# Flyback_circuit_2024-07-31.net
KiCad netlist of a schematic drawn in EasyEDA Pro
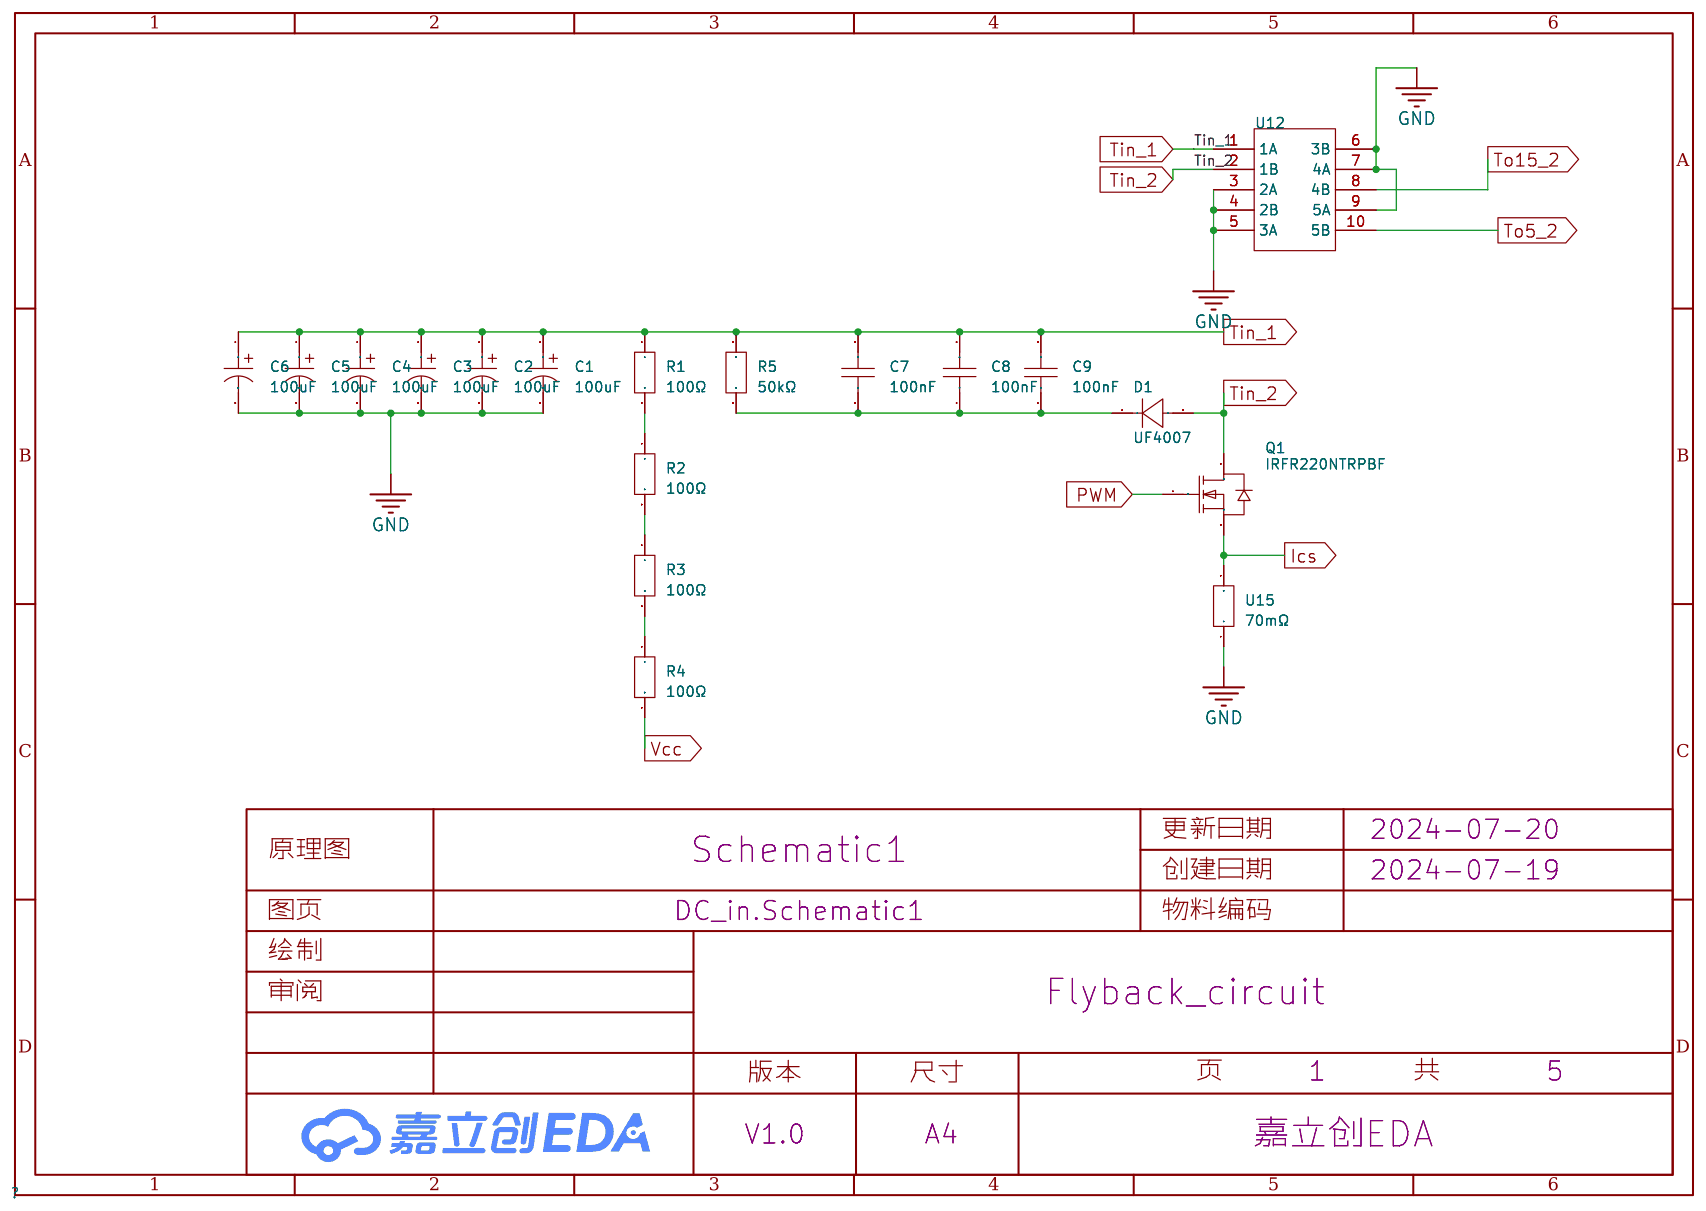
[diagram p0: DC_in]
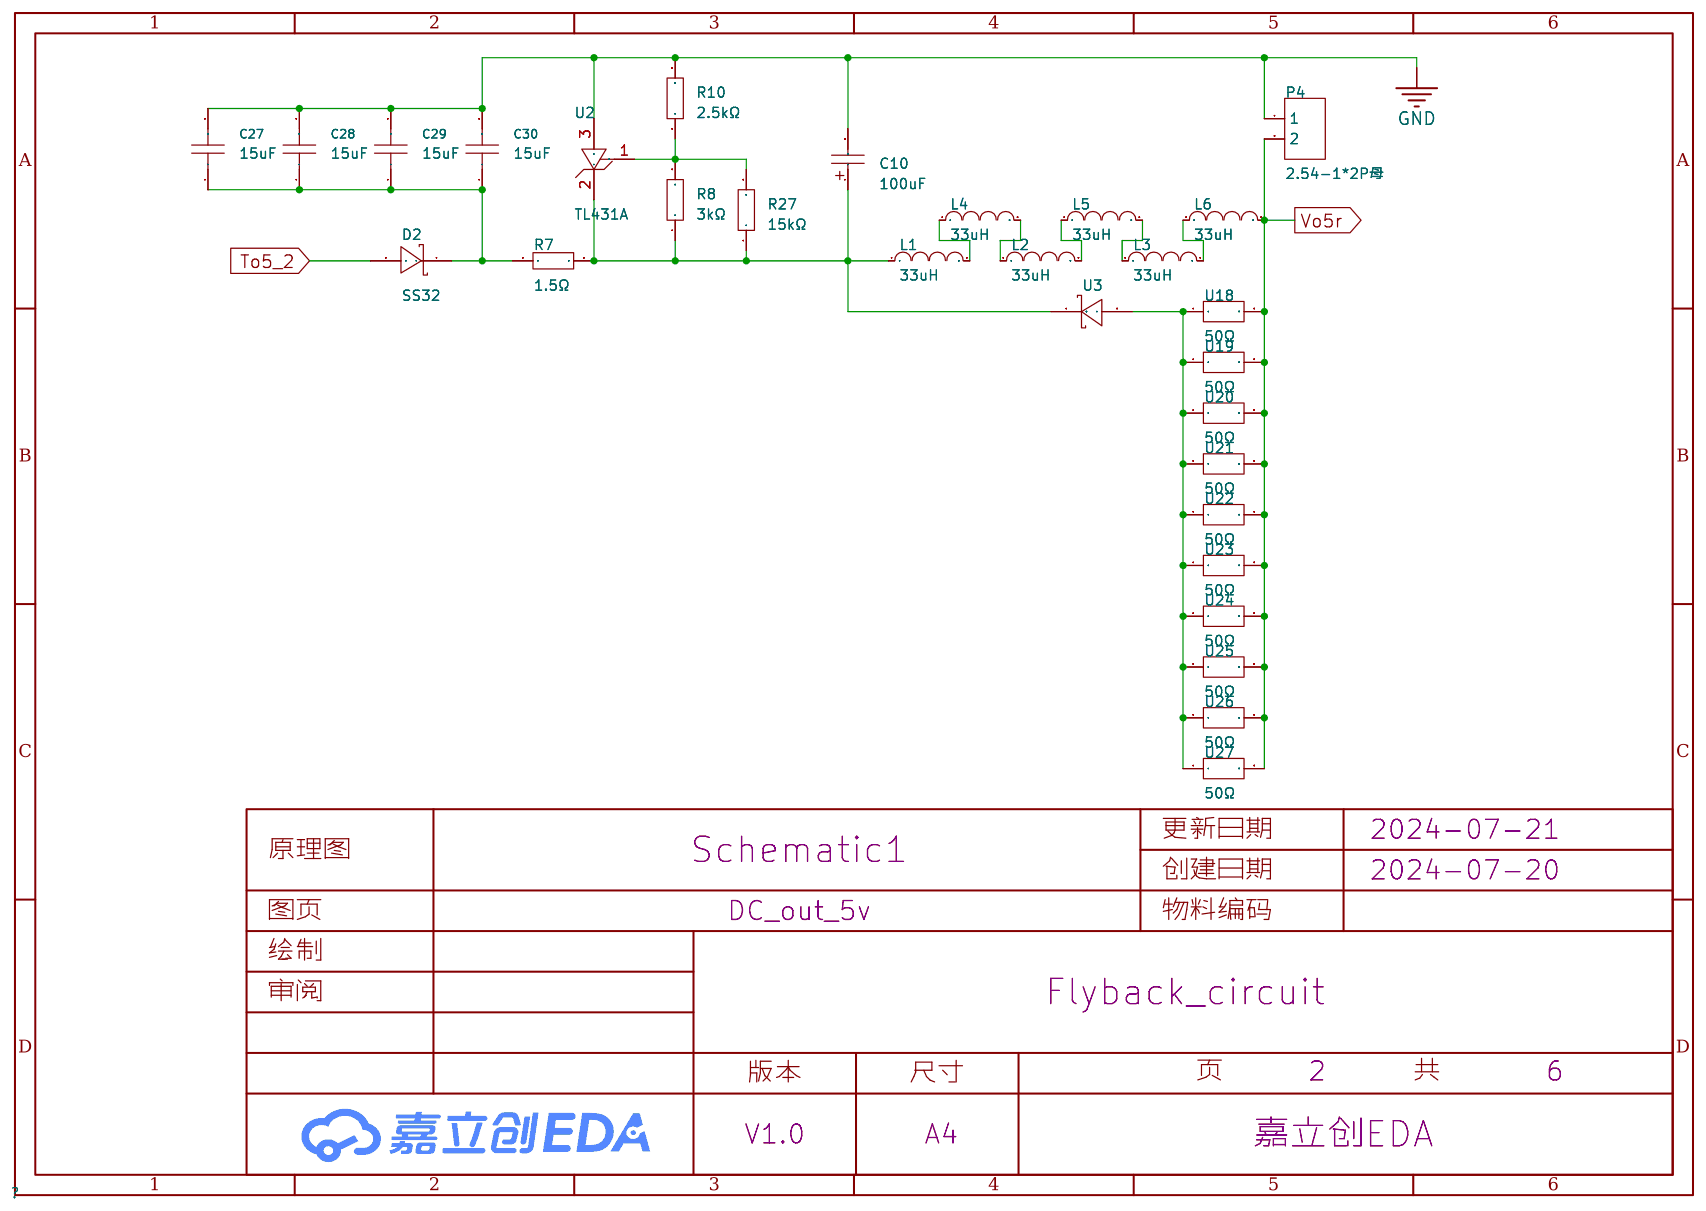
[diagram p1: DC_out_5v]
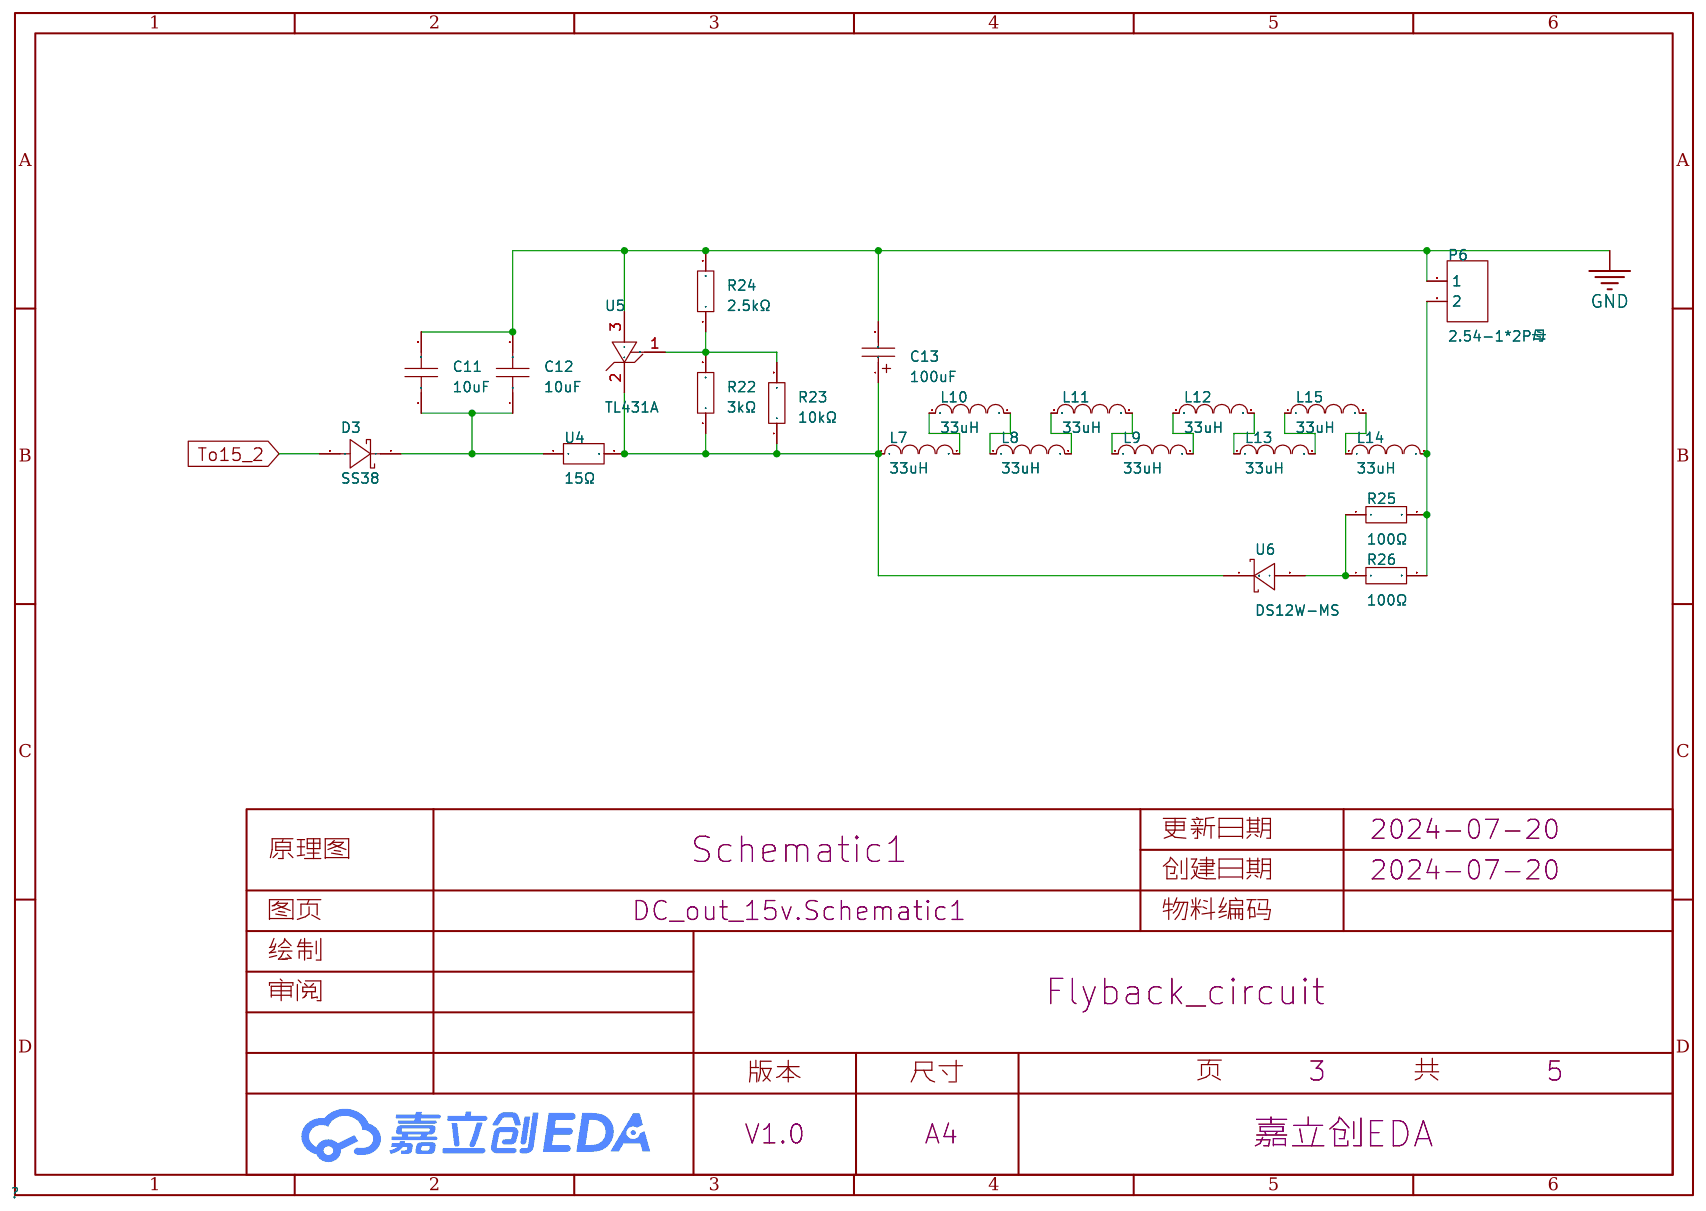
[diagram p2: DC_out_15v]
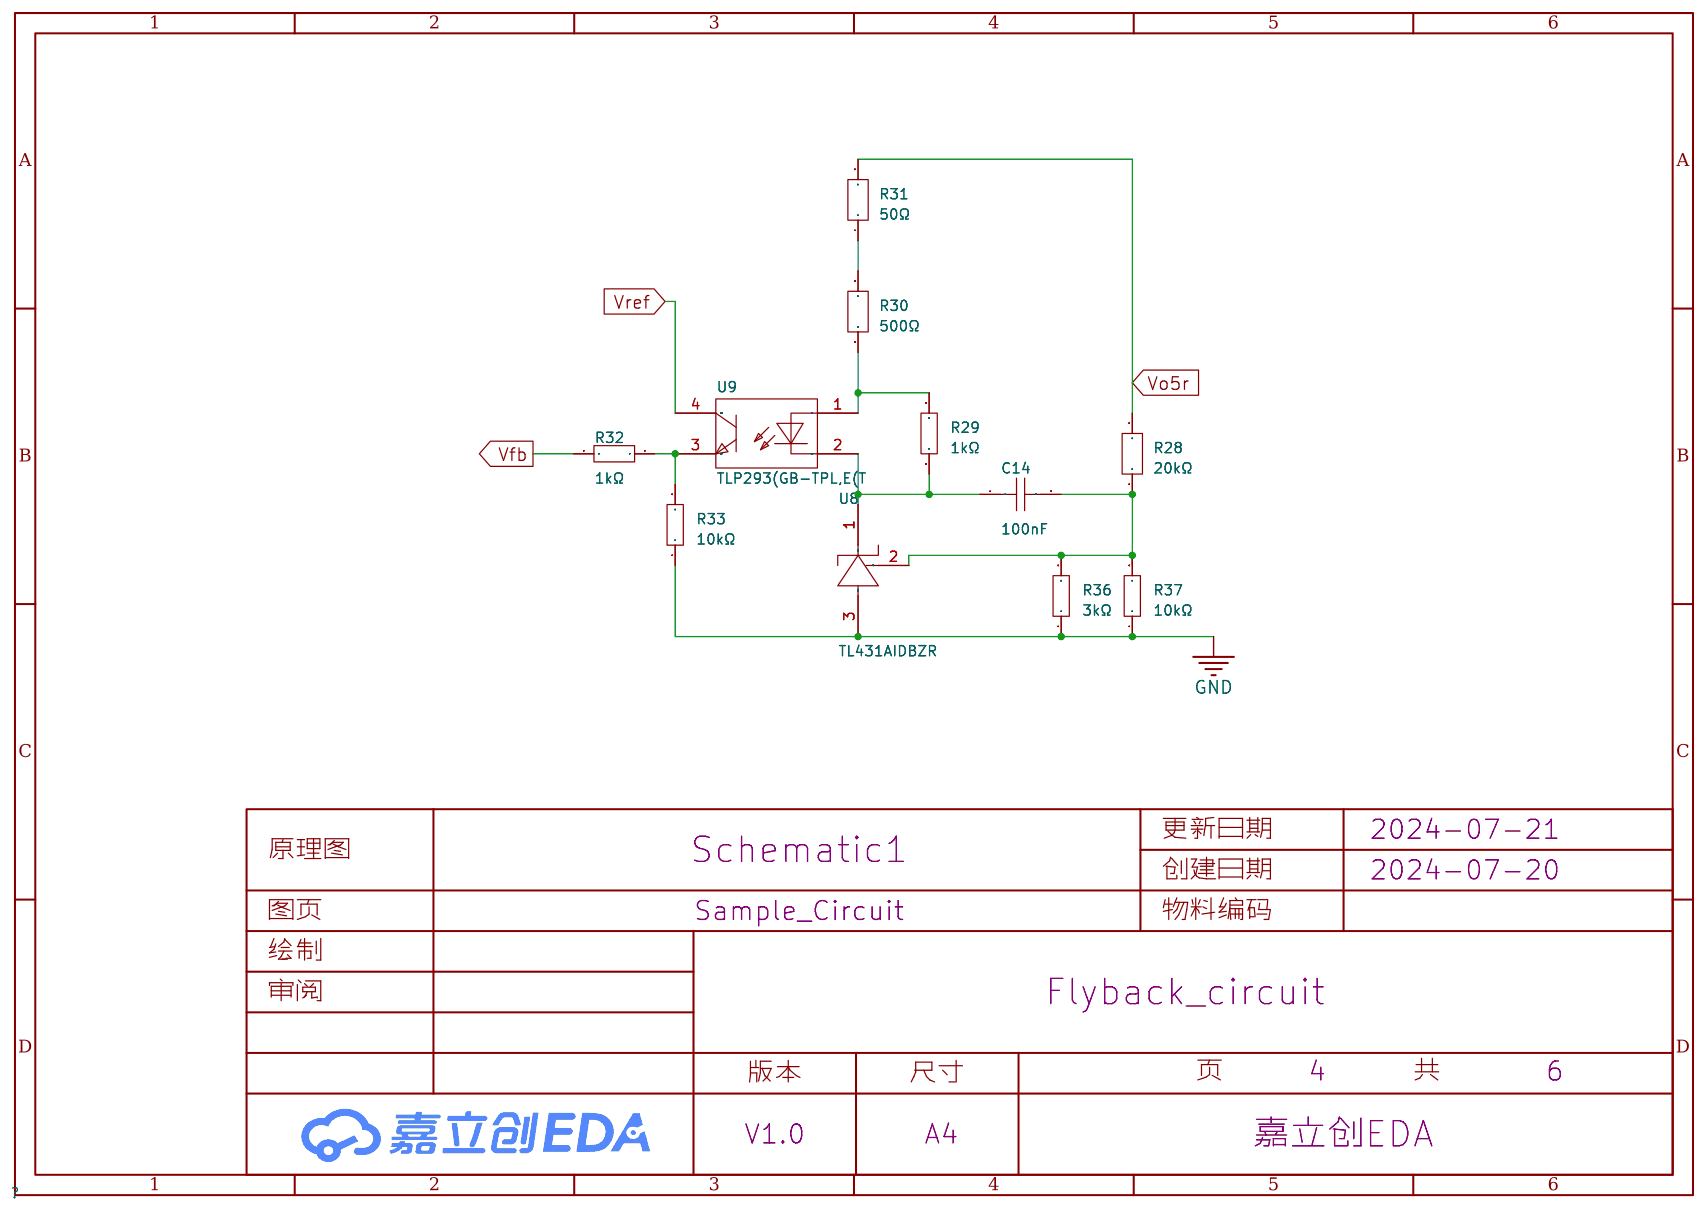
[diagram p3: Sample_Circuit]
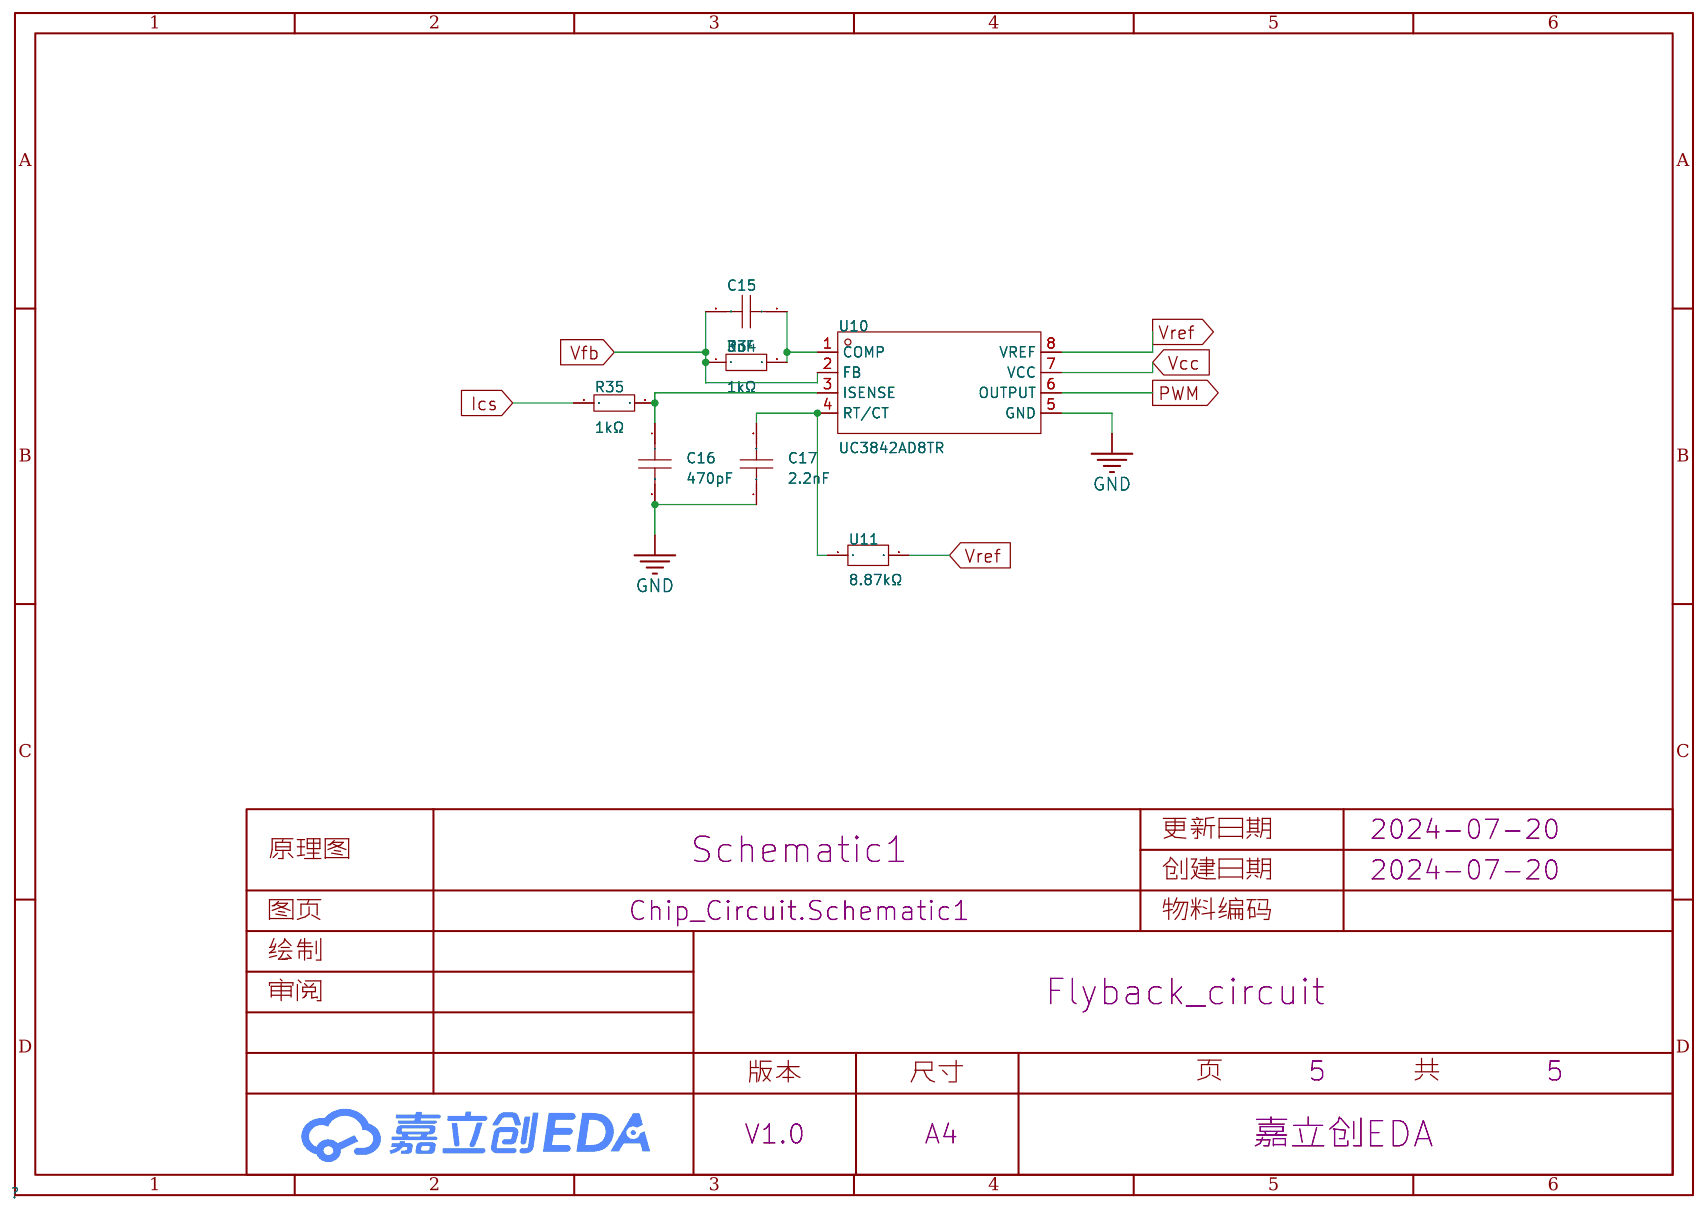
[diagram p4: Chip_Circuit]
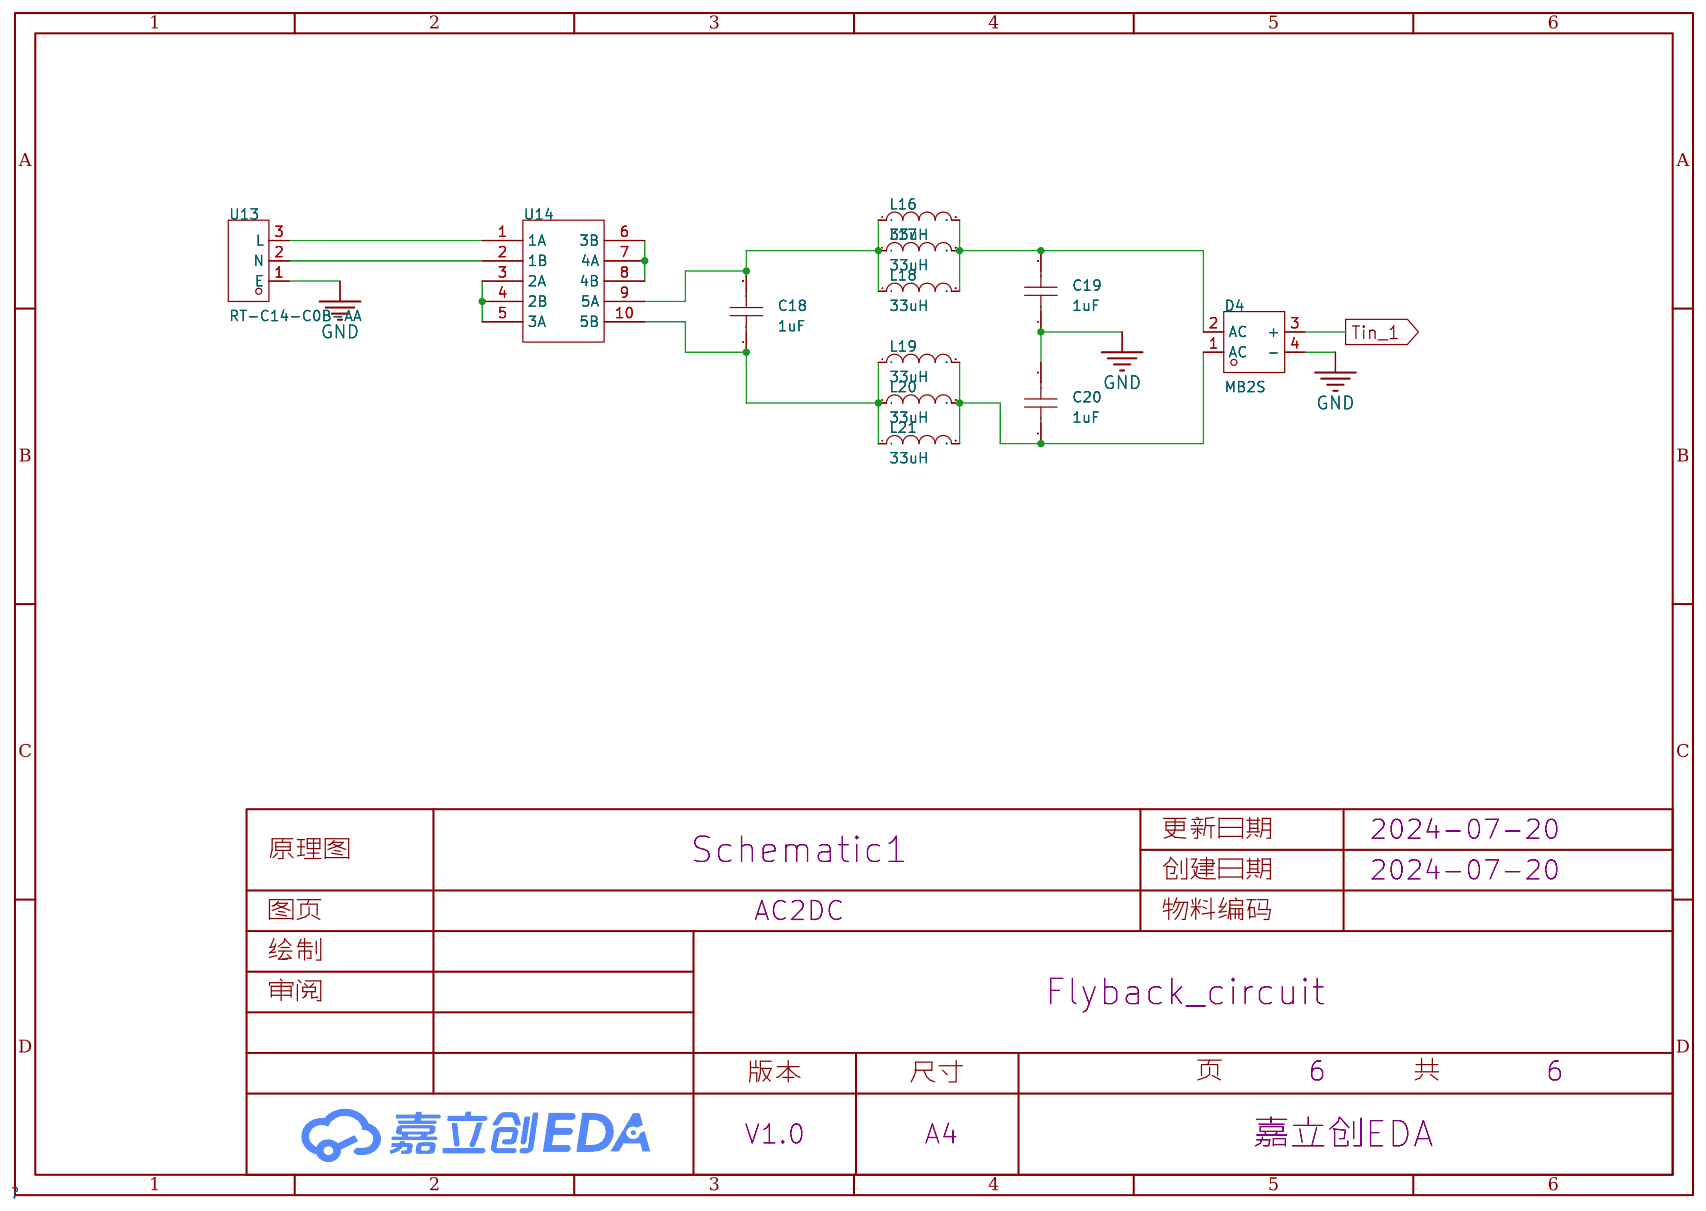
[diagram p5: AC2DC]

(export (version "E")
  (design (tool "Eeschema 10.0.6"))
  (components
    (comp (ref "C1")
      (value "100uF")
      (footprint "easyedapro:CAP-SMD_BD6.3-L6.6-W6.6-LS7.4-FD")
      (description "容值:100uF;精度:±20%;额定电压:35V;纹波电流:87mA@120kHz;等效串联电阻:-;")
      (fields
        (field (name "Manufacturer Part") "RVT100UF35V67RV0034")
        (field (name "Manufacturer") "KNSCHA(科尼盛)")
      )
      (libsource (lib "easyedapro") (part "RVT100UF35V67RV0034"))
    )
    (comp (ref "C2")
      (value "100uF")
      (footprint "easyedapro:CAP-SMD_BD6.3-L6.6-W6.6-LS7.4-FD")
      (description "容值:100uF;精度:±20%;额定电压:35V;纹波电流:87mA@120kHz;等效串联电阻:-;")
      (fields
        (field (name "Manufacturer Part") "RVT100UF35V67RV0034")
        (field (name "Manufacturer") "KNSCHA(科尼盛)")
      )
      (libsource (lib "easyedapro") (part "RVT100UF35V67RV0034"))
    )
    (comp (ref "C3")
      (value "100uF")
      (footprint "easyedapro:CAP-SMD_BD6.3-L6.6-W6.6-LS7.4-FD")
      (description "容值:100uF;精度:±20%;额定电压:35V;纹波电流:87mA@120kHz;等效串联电阻:-;")
      (fields
        (field (name "Manufacturer Part") "RVT100UF35V67RV0034")
        (field (name "Manufacturer") "KNSCHA(科尼盛)")
      )
      (libsource (lib "easyedapro") (part "RVT100UF35V67RV0034"))
    )
    (comp (ref "C4")
      (value "100uF")
      (footprint "easyedapro:CAP-SMD_BD6.3-L6.6-W6.6-LS7.4-FD")
      (description "容值:100uF;精度:±20%;额定电压:35V;纹波电流:87mA@120kHz;等效串联电阻:-;")
      (fields
        (field (name "Manufacturer Part") "RVT100UF35V67RV0034")
        (field (name "Manufacturer") "KNSCHA(科尼盛)")
      )
      (libsource (lib "easyedapro") (part "RVT100UF35V67RV0034"))
    )
    (comp (ref "C5")
      (value "100uF")
      (footprint "easyedapro:CAP-SMD_BD6.3-L6.6-W6.6-LS7.4-FD")
      (description "容值:100uF;精度:±20%;额定电压:35V;纹波电流:87mA@120kHz;等效串联电阻:-;")
      (fields
        (field (name "Manufacturer Part") "RVT100UF35V67RV0034")
        (field (name "Manufacturer") "KNSCHA(科尼盛)")
      )
      (libsource (lib "easyedapro") (part "RVT100UF35V67RV0034"))
    )
    (comp (ref "C6")
      (value "100uF")
      (footprint "easyedapro:CAP-SMD_BD6.3-L6.6-W6.6-LS7.4-FD")
      (description "容值:100uF;精度:±20%;额定电压:35V;纹波电流:87mA@120kHz;等效串联电阻:-;")
      (fields
        (field (name "Manufacturer Part") "RVT100UF35V67RV0034")
        (field (name "Manufacturer") "KNSCHA(科尼盛)")
      )
      (libsource (lib "easyedapro") (part "RVT100UF35V67RV0034"))
    )
    (comp (ref "C7")
      (value "100nF")
      (footprint "easyedapro:C0603")
      (description "容值:100nF;精度:±10%;额定电压:50V;材质(温度系数):X7R;")
      (fields
        (field (name "Manufacturer Part") "CC0603KRX7R9BB104")
        (field (name "Manufacturer") "YAGEO(国巨)")
      )
      (libsource (lib "easyedapro") (part "CC0603KRX7R9BB104"))
    )
    (comp (ref "C8")
      (value "100nF")
      (footprint "easyedapro:C0603")
      (description "容值:100nF;精度:±10%;额定电压:50V;材质(温度系数):X7R;")
      (fields
        (field (name "Manufacturer Part") "CC0603KRX7R9BB104")
        (field (name "Manufacturer") "YAGEO(国巨)")
      )
      (libsource (lib "easyedapro") (part "CC0603KRX7R9BB104"))
    )
    (comp (ref "C9")
      (value "100nF")
      (footprint "easyedapro:C0603")
      (description "容值:100nF;精度:±10%;额定电压:50V;材质(温度系数):X7R;")
      (fields
        (field (name "Manufacturer Part") "CC0603KRX7R9BB104")
        (field (name "Manufacturer") "YAGEO(国巨)")
      )
      (libsource (lib "easyedapro") (part "CC0603KRX7R9BB104"))
    )
    (comp (ref "D1")
      (value "UF4007")
      (footprint "easyedapro:DO-41_BD2.4-L4.7-P8.70-D0.9-RD")
      (description "二极管配置:-;正向压降(Vf):1.7V@1A;直流反向耐压(Vr):1kV;整流电流:1A;反向恢复时间(trr):75ns;")
      (fields (field (name "Manufacturer") "MDD(辰达半导体)"))
      (libsource (lib "easyedapro") (part "UF4007_C960666"))
    )
    (comp (ref "Q1")
      (value "IRFR220NTRPBF")
      (footprint "easyedapro:TO-252-2_L6.6-W6.1-P4.57-LS9.9-TR-CW")
      (fields (field (name "Manufacturer") "Infineon(英飞凌)"))
      (libsource (lib "easyedapro") (part "IRFR220N"))
    )
    (comp (ref "R1")
      (value "100Ω")
      (footprint "easyedapro:R2010")
      (description "电阻类型:厚膜电阻;阻值:100Ω;精度:±5%;功率:1.5W;最大工作电压:400V;温度系数:±100ppm/°C;")
      (fields
        (field (name "Manufacturer Part") "AS101AJ0101T4E")
        (field (name "Manufacturer") "UNI-ROYAL(厚声)")
      )
      (libsource (lib "easyedapro") (part "AS101AJ0101T4E"))
    )
    (comp (ref "R2")
      (value "100Ω")
      (footprint "easyedapro:R2010")
      (description "电阻类型:厚膜电阻;阻值:100Ω;精度:±5%;功率:1.5W;最大工作电压:400V;温度系数:±100ppm/°C;")
      (fields
        (field (name "Manufacturer Part") "AS101AJ0101T4E")
        (field (name "Manufacturer") "UNI-ROYAL(厚声)")
      )
      (libsource (lib "easyedapro") (part "AS101AJ0101T4E"))
    )
    (comp (ref "R3")
      (value "100Ω")
      (footprint "easyedapro:R2010")
      (description "电阻类型:厚膜电阻;阻值:100Ω;精度:±5%;功率:1.5W;最大工作电压:400V;温度系数:±100ppm/°C;")
      (fields
        (field (name "Manufacturer Part") "AS101AJ0101T4E")
        (field (name "Manufacturer") "UNI-ROYAL(厚声)")
      )
      (libsource (lib "easyedapro") (part "AS101AJ0101T4E"))
    )
    (comp (ref "R4")
      (value "100Ω")
      (footprint "easyedapro:R2010")
      (description "电阻类型:厚膜电阻;阻值:100Ω;精度:±5%;功率:1.5W;最大工作电压:400V;温度系数:±100ppm/°C;")
      (fields
        (field (name "Manufacturer Part") "AS101AJ0101T4E")
        (field (name "Manufacturer") "UNI-ROYAL(厚声)")
      )
      (libsource (lib "easyedapro") (part "AS101AJ0101T4E"))
    )
    (comp (ref "R5")
      (value "50kΩ")
      (footprint "easyedapro:R0805")
      (description "电阻类型:薄膜电阻;阻值:50kΩ;精度:±0.5%;功率:125mW;最大工作电压:150V;温度系数:±25ppm/°C;")
      (fields (field (name "Manufacturer Part") "ARG05DTC5002") (field (name "Manufacturer") "Viking(光颉)"))
      (libsource (lib "easyedapro") (part "ARG05DTC5002"))
    )
    (comp (ref "U12")
      (value "~")
      (footprint "easyedapro:反激变压器_封装")
      (libsource (lib "easyedapro") (part "反激变压器_自定义"))
    )
    (comp (ref "U15")
      (value "70mΩ")
      (footprint "easyedapro:R1206")
      (description "电阻类型:薄膜电阻;阻值:70mΩ;精度:±1%;功率:500mW;最大工作电压:-;温度系数:±75ppm/°C;")
      (fields (field (name "Manufacturer Part") "PE1206FRM7W0R07L") (field (name "Manufacturer") "YAGEO(国巨)"))
      (libsource (lib "easyedapro") (part "PE1206FRM7W0R07L"))
    )
    (comp (ref "C10")
      (value "100uF")
      (footprint "easyedapro:CAP-SMD_L3.5-W2.8-R-RD")
      (description "容值:100uF;精度:±10%;额定电压:10V;等效串联电阻:1.4Ω@100kHz;")
      (fields (field (name "Manufacturer Part") "CA45-B010K107T") (field (name "Manufacturer") "湘怡中元/湘江"))
      (libsource (lib "easyedapro") (part "CA45-B010K107T"))
    )
    (comp (ref "C27")
      (value "15uF")
      (footprint "easyedapro:CAP-TH_L5.5-W4.0-P2.50-D1.0")
      (description "容值:15uF;精度:±20%;额定电压:16V;温度系数:X7R;")
      (fields (field (name "Manufacturer Part") "FG11X7R1C156MRT06") (field (name "Manufacturer") "TDK"))
      (libsource (lib "easyedapro") (part "FG11X7R1C156MRT06"))
    )
    (comp (ref "C28")
      (value "15uF")
      (footprint "easyedapro:CAP-TH_L5.5-W4.0-P2.50-D1.0")
      (description "容值:15uF;精度:±20%;额定电压:16V;温度系数:X7R;")
      (fields (field (name "Manufacturer Part") "FG11X7R1C156MRT06") (field (name "Manufacturer") "TDK"))
      (libsource (lib "easyedapro") (part "FG11X7R1C156MRT06"))
    )
    (comp (ref "C29")
      (value "15uF")
      (footprint "easyedapro:CAP-TH_L5.5-W4.0-P2.50-D1.0")
      (description "容值:15uF;精度:±20%;额定电压:16V;温度系数:X7R;")
      (fields (field (name "Manufacturer Part") "FG11X7R1C156MRT06") (field (name "Manufacturer") "TDK"))
      (libsource (lib "easyedapro") (part "FG11X7R1C156MRT06"))
    )
    (comp (ref "C30")
      (value "15uF")
      (footprint "easyedapro:CAP-TH_L5.5-W4.0-P2.50-D1.0")
      (description "容值:15uF;精度:±20%;额定电压:16V;温度系数:X7R;")
      (fields (field (name "Manufacturer Part") "FG11X7R1C156MRT06") (field (name "Manufacturer") "TDK"))
      (libsource (lib "easyedapro") (part "FG11X7R1C156MRT06"))
    )
    (comp (ref "D2")
      (value "SS32")
      (footprint "easyedapro:SMA_L4.3-W2.6-LS5.2-RD")
      (description "二极管配置:独立式;正向压降(Vf):550mV@3A;直流反向耐压(Vr):20V;整流电流:3A;")
      (fields (field (name "Manufacturer") "MDD(辰达半导体)"))
      (libsource (lib "easyedapro") (part "SS32_C34897"))
    )
    (comp (ref "L1")
      (value "33uH")
      (footprint "easyedapro:IND-SMD_L7.0-W6.6_FXL0630")
      (description "电感值:33uH;精度:±20%;额定电流:2A;饱和电流(Isat):2.5A;类型:一体成型电感;")
      (fields (field (name "Manufacturer Part") "FXL0630-330-M") (field (name "Manufacturer") "cjiang(长江微电)"))
      (libsource (lib "easyedapro") (part "FXL0630-330-M"))
    )
    (comp (ref "L2")
      (value "33uH")
      (footprint "easyedapro:IND-SMD_L7.0-W6.6_FXL0630")
      (description "电感值:33uH;精度:±20%;额定电流:2A;饱和电流(Isat):2.5A;类型:一体成型电感;")
      (fields (field (name "Manufacturer Part") "FXL0630-330-M") (field (name "Manufacturer") "cjiang(长江微电)"))
      (libsource (lib "easyedapro") (part "FXL0630-330-M"))
    )
    (comp (ref "L3")
      (value "33uH")
      (footprint "easyedapro:IND-SMD_L7.0-W6.6_FXL0630")
      (description "电感值:33uH;精度:±20%;额定电流:2A;饱和电流(Isat):2.5A;类型:一体成型电感;")
      (fields (field (name "Manufacturer Part") "FXL0630-330-M") (field (name "Manufacturer") "cjiang(长江微电)"))
      (libsource (lib "easyedapro") (part "FXL0630-330-M"))
    )
    (comp (ref "L4")
      (value "33uH")
      (footprint "easyedapro:IND-SMD_L7.0-W6.6_FXL0630")
      (description "电感值:33uH;精度:±20%;额定电流:2A;饱和电流(Isat):2.5A;类型:一体成型电感;")
      (fields (field (name "Manufacturer Part") "FXL0630-330-M") (field (name "Manufacturer") "cjiang(长江微电)"))
      (libsource (lib "easyedapro") (part "FXL0630-330-M"))
    )
    (comp (ref "L5")
      (value "33uH")
      (footprint "easyedapro:IND-SMD_L7.0-W6.6_FXL0630")
      (description "电感值:33uH;精度:±20%;额定电流:2A;饱和电流(Isat):2.5A;类型:一体成型电感;")
      (fields (field (name "Manufacturer Part") "FXL0630-330-M") (field (name "Manufacturer") "cjiang(长江微电)"))
      (libsource (lib "easyedapro") (part "FXL0630-330-M"))
    )
    (comp (ref "L6")
      (value "33uH")
      (footprint "easyedapro:IND-SMD_L7.0-W6.6_FXL0630")
      (description "电感值:33uH;精度:±20%;额定电流:2A;饱和电流(Isat):2.5A;类型:一体成型电感;")
      (fields (field (name "Manufacturer Part") "FXL0630-330-M") (field (name "Manufacturer") "cjiang(长江微电)"))
      (libsource (lib "easyedapro") (part "FXL0630-330-M"))
    )
    (comp (ref "P4")
      (value "2.54-1*2P母")
      (footprint "easyedapro:HDR-TH_2P-P2.54-V-F")
      (description "插孔结构:1x2P;间距:2.54mm;行距:-;安装类型:直插;排数:单排;总孔位数:2P;塑高:-;触头材质:-;触头镀层:-;")
      (fields (field (name "Manufacturer") "BOOMELE(博穆精密)"))
      (libsource (lib "easyedapro") (part "Header-Female-2.54_1x2"))
    )
    (comp (ref "R7")
      (value "1.5Ω")
      (footprint "easyedapro:RES-TH_BD1.9-L3.3-P7.30-D0.5")
      (description "电阻类型:金属膜电阻;阻值:1.5Ω;精度:±1%;功率:166.667mW;温度系数:±100ppm/°C;")
      (fields (field (name "Manufacturer Part") "RN16T51R50F") (field (name "Manufacturer") "大毅科技"))
      (libsource (lib "easyedapro") (part "RN16T51R50F"))
    )
    (comp (ref "R8")
      (value "3kΩ")
      (footprint "easyedapro:R0402")
      (description "电阻类型:薄膜电阻;阻值:3kΩ;精度:±0.1%;功率:62.5mW;最大工作电压:50V;温度系数:±25ppm/°C;")
      (fields (field (name "Manufacturer Part") "RT0402BRD073KL") (field (name "Manufacturer") "YAGEO(国巨)"))
      (libsource (lib "easyedapro") (part "RT0402BRD073KL"))
    )
    (comp (ref "R10")
      (value "2.5kΩ")
      (footprint "easyedapro:R0603")
      (description "阻值:2.5kΩ;精度:±0.1%;功率:62.5mW;温度系数:±25ppm/°C;")
      (fields (field (name "Manufacturer Part") "AR03BTC2501") (field (name "Manufacturer") "Viking(光颉)"))
      (libsource (lib "easyedapro") (part "AR03BTC2501"))
    )
    (comp (ref "R27")
      (value "15kΩ")
      (footprint "easyedapro:R0603")
      (description "电阻类型:厚膜电阻;阻值:15kΩ;精度:±1%;功率:100mW;最大工作电压:75V;温度系数:±100ppm/°C;")
      (fields
        (field (name "Manufacturer Part") "0603WAF1502T5E")
        (field (name "Manufacturer") "UNI-ROYAL(厚声)")
      )
      (libsource (lib "easyedapro") (part "0603WAF1502T5E"))
    )
    (comp (ref "U2")
      (value "TL431A")
      (footprint "easyedapro:SOT-23-3_L2.9-W1.3-P1.90-LS2.4-BR")
      (description "输出类型:可调;输入电压:37V;输出电压:2.495V~36V;输出电流:100mA;精度:±0.5%;")
      (fields (field (name "Manufacturer") "PJSEMI(平晶微)"))
      (libsource (lib "easyedapro") (part "TL431A_C411753"))
    )
    (comp (ref "U3")
      (value "DS12W-MS")
      (footprint "easyedapro:SOD-123FL_L2.7-W1.8-LS3.8-RD")
      (description "二极管配置:独立式;正向压降(Vf):550mV@1A;直流反向耐压(Vr):20V;平均整流电流(Io):1A;")
      (fields (field (name "Manufacturer") "MSKSEMI(美森科)"))
      (libsource (lib "easyedapro") (part "DS12W-MS"))
    )
    (comp (ref "U18")
      (value "50Ω")
      (footprint "easyedapro:R0603")
      (description "电阻类型:薄膜电阻;阻值:50Ω;精度:±0.1%;功率:100mW;温度系数:±50ppm/°C;")
      (fields (field (name "Manufacturer Part") "RT0603BRE0750RL") (field (name "Manufacturer") "YAGEO(国巨)"))
      (libsource (lib "easyedapro") (part "RT0603BRE0750RL"))
    )
    (comp (ref "U19")
      (value "50Ω")
      (footprint "easyedapro:R0603")
      (description "电阻类型:薄膜电阻;阻值:50Ω;精度:±0.1%;功率:100mW;温度系数:±50ppm/°C;")
      (fields (field (name "Manufacturer Part") "RT0603BRE0750RL") (field (name "Manufacturer") "YAGEO(国巨)"))
      (libsource (lib "easyedapro") (part "RT0603BRE0750RL"))
    )
    (comp (ref "U20")
      (value "50Ω")
      (footprint "easyedapro:R0603")
      (description "电阻类型:薄膜电阻;阻值:50Ω;精度:±0.1%;功率:100mW;温度系数:±50ppm/°C;")
      (fields (field (name "Manufacturer Part") "RT0603BRE0750RL") (field (name "Manufacturer") "YAGEO(国巨)"))
      (libsource (lib "easyedapro") (part "RT0603BRE0750RL"))
    )
    (comp (ref "U21")
      (value "50Ω")
      (footprint "easyedapro:R0603")
      (description "电阻类型:薄膜电阻;阻值:50Ω;精度:±0.1%;功率:100mW;温度系数:±50ppm/°C;")
      (fields (field (name "Manufacturer Part") "RT0603BRE0750RL") (field (name "Manufacturer") "YAGEO(国巨)"))
      (libsource (lib "easyedapro") (part "RT0603BRE0750RL"))
    )
    (comp (ref "U22")
      (value "50Ω")
      (footprint "easyedapro:R0603")
      (description "电阻类型:薄膜电阻;阻值:50Ω;精度:±0.1%;功率:100mW;温度系数:±50ppm/°C;")
      (fields (field (name "Manufacturer Part") "RT0603BRE0750RL") (field (name "Manufacturer") "YAGEO(国巨)"))
      (libsource (lib "easyedapro") (part "RT0603BRE0750RL"))
    )
    (comp (ref "U23")
      (value "50Ω")
      (footprint "easyedapro:R0603")
      (description "电阻类型:薄膜电阻;阻值:50Ω;精度:±0.1%;功率:100mW;温度系数:±50ppm/°C;")
      (fields (field (name "Manufacturer Part") "RT0603BRE0750RL") (field (name "Manufacturer") "YAGEO(国巨)"))
      (libsource (lib "easyedapro") (part "RT0603BRE0750RL"))
    )
    (comp (ref "U24")
      (value "50Ω")
      (footprint "easyedapro:R0603")
      (description "电阻类型:薄膜电阻;阻值:50Ω;精度:±0.1%;功率:100mW;温度系数:±50ppm/°C;")
      (fields (field (name "Manufacturer Part") "RT0603BRE0750RL") (field (name "Manufacturer") "YAGEO(国巨)"))
      (libsource (lib "easyedapro") (part "RT0603BRE0750RL"))
    )
    (comp (ref "U25")
      (value "50Ω")
      (footprint "easyedapro:R0603")
      (description "电阻类型:薄膜电阻;阻值:50Ω;精度:±0.1%;功率:100mW;温度系数:±50ppm/°C;")
      (fields (field (name "Manufacturer Part") "RT0603BRE0750RL") (field (name "Manufacturer") "YAGEO(国巨)"))
      (libsource (lib "easyedapro") (part "RT0603BRE0750RL"))
    )
    (comp (ref "U26")
      (value "50Ω")
      (footprint "easyedapro:R0603")
      (description "电阻类型:薄膜电阻;阻值:50Ω;精度:±0.1%;功率:100mW;温度系数:±50ppm/°C;")
      (fields (field (name "Manufacturer Part") "RT0603BRE0750RL") (field (name "Manufacturer") "YAGEO(国巨)"))
      (libsource (lib "easyedapro") (part "RT0603BRE0750RL"))
    )
    (comp (ref "U27")
      (value "50Ω")
      (footprint "easyedapro:R0603")
      (description "电阻类型:薄膜电阻;阻值:50Ω;精度:±0.1%;功率:100mW;温度系数:±50ppm/°C;")
      (fields (field (name "Manufacturer Part") "RT0603BRE0750RL") (field (name "Manufacturer") "YAGEO(国巨)"))
      (libsource (lib "easyedapro") (part "RT0603BRE0750RL"))
    )
    (comp (ref "C11")
      (value "10uF")
      (footprint "easyedapro:C1210")
      (description "容值:10uF;精度:±10%;额定电压:100V;材质(温度系数):X7R;")
      (fields (field (name "Manufacturer Part") "FS32X106K101EGG") (field (name "Manufacturer") "PSA(信昌电陶)"))
      (libsource (lib "easyedapro") (part "FS32X106K101EGG"))
    )
    (comp (ref "C12")
      (value "10uF")
      (footprint "easyedapro:C1210")
      (description "容值:10uF;精度:±10%;额定电压:100V;材质(温度系数):X7R;")
      (fields (field (name "Manufacturer Part") "FS32X106K101EGG") (field (name "Manufacturer") "PSA(信昌电陶)"))
      (libsource (lib "easyedapro") (part "FS32X106K101EGG"))
    )
    (comp (ref "C13")
      (value "100uF")
      (footprint "easyedapro:CASE-D_7343")
      (description "容值:100uF;精度:±10%;额定电压:20V;等效串联电阻:500mΩ@100kHz;")
      (fields (field (name "Manufacturer Part") "TAJD107K020RNJ") (field (name "Manufacturer") "Kyocera AVX"))
      (libsource (lib "easyedapro") (part "TAJD107K020RNJ"))
    )
    (comp (ref "D3")
      (value "SS38")
      (footprint "easyedapro:SMA_L4.3-W2.6-LS5.0-RD")
      (description "二极管配置:独立式;正向压降(Vf):850mV@3A;直流反向耐压(Vr):80V;平均整流电流(Io):3A;")
      (fields (field (name "Manufacturer") "宏迦橙"))
      (libsource (lib "easyedapro") (part "SS38_C18199196"))
    )
    (comp (ref "L7")
      (value "33uH")
      (footprint "easyedapro:IND-SMD_L7.0-W6.6_FXL0630")
      (description "电感值:33uH;精度:±20%;额定电流:2A;饱和电流(Isat):2.5A;类型:一体成型电感;")
      (fields (field (name "Manufacturer Part") "FXL0630-330-M") (field (name "Manufacturer") "cjiang(长江微电)"))
      (libsource (lib "easyedapro") (part "FXL0630-330-M"))
    )
    (comp (ref "L8")
      (value "33uH")
      (footprint "easyedapro:IND-SMD_L7.0-W6.6_FXL0630")
      (description "电感值:33uH;精度:±20%;额定电流:2A;饱和电流(Isat):2.5A;类型:一体成型电感;")
      (fields (field (name "Manufacturer Part") "FXL0630-330-M") (field (name "Manufacturer") "cjiang(长江微电)"))
      (libsource (lib "easyedapro") (part "FXL0630-330-M"))
    )
    (comp (ref "L9")
      (value "33uH")
      (footprint "easyedapro:IND-SMD_L7.0-W6.6_FXL0630")
      (description "电感值:33uH;精度:±20%;额定电流:2A;饱和电流(Isat):2.5A;类型:一体成型电感;")
      (fields (field (name "Manufacturer Part") "FXL0630-330-M") (field (name "Manufacturer") "cjiang(长江微电)"))
      (libsource (lib "easyedapro") (part "FXL0630-330-M"))
    )
    (comp (ref "L10")
      (value "33uH")
      (footprint "easyedapro:IND-SMD_L7.0-W6.6_FXL0630")
      (description "电感值:33uH;精度:±20%;额定电流:2A;饱和电流(Isat):2.5A;类型:一体成型电感;")
      (fields (field (name "Manufacturer Part") "FXL0630-330-M") (field (name "Manufacturer") "cjiang(长江微电)"))
      (libsource (lib "easyedapro") (part "FXL0630-330-M"))
    )
    (comp (ref "L11")
      (value "33uH")
      (footprint "easyedapro:IND-SMD_L7.0-W6.6_FXL0630")
      (description "电感值:33uH;精度:±20%;额定电流:2A;饱和电流(Isat):2.5A;类型:一体成型电感;")
      (fields (field (name "Manufacturer Part") "FXL0630-330-M") (field (name "Manufacturer") "cjiang(长江微电)"))
      (libsource (lib "easyedapro") (part "FXL0630-330-M"))
    )
    (comp (ref "L12")
      (value "33uH")
      (footprint "easyedapro:IND-SMD_L7.0-W6.6_FXL0630")
      (description "电感值:33uH;精度:±20%;额定电流:2A;饱和电流(Isat):2.5A;类型:一体成型电感;")
      (fields (field (name "Manufacturer Part") "FXL0630-330-M") (field (name "Manufacturer") "cjiang(长江微电)"))
      (libsource (lib "easyedapro") (part "FXL0630-330-M"))
    )
    (comp (ref "L13")
      (value "33uH")
      (footprint "easyedapro:IND-SMD_L7.0-W6.6_FXL0630")
      (description "电感值:33uH;精度:±20%;额定电流:2A;饱和电流(Isat):2.5A;类型:一体成型电感;")
      (fields (field (name "Manufacturer Part") "FXL0630-330-M") (field (name "Manufacturer") "cjiang(长江微电)"))
      (libsource (lib "easyedapro") (part "FXL0630-330-M"))
    )
    (comp (ref "L14")
      (value "33uH")
      (footprint "easyedapro:IND-SMD_L7.0-W6.6_FXL0630")
      (description "电感值:33uH;精度:±20%;额定电流:2A;饱和电流(Isat):2.5A;类型:一体成型电感;")
      (fields (field (name "Manufacturer Part") "FXL0630-330-M") (field (name "Manufacturer") "cjiang(长江微电)"))
      (libsource (lib "easyedapro") (part "FXL0630-330-M"))
    )
    (comp (ref "L15")
      (value "33uH")
      (footprint "easyedapro:IND-SMD_L7.0-W6.6_FXL0630")
      (description "电感值:33uH;精度:±20%;额定电流:2A;饱和电流(Isat):2.5A;类型:一体成型电感;")
      (fields (field (name "Manufacturer Part") "FXL0630-330-M") (field (name "Manufacturer") "cjiang(长江微电)"))
      (libsource (lib "easyedapro") (part "FXL0630-330-M"))
    )
    (comp (ref "P6")
      (value "2.54-1*2P母")
      (footprint "easyedapro:HDR-TH_2P-P2.54-V-F")
      (description "插孔结构:1x2P;间距:2.54mm;行距:-;安装类型:直插;排数:单排;总孔位数:2P;塑高:-;触头材质:-;触头镀层:-;")
      (fields (field (name "Manufacturer") "BOOMELE(博穆精密)"))
      (libsource (lib "easyedapro") (part "Header-Female-2.54_1x2"))
    )
    (comp (ref "R22")
      (value "3kΩ")
      (footprint "easyedapro:R0402")
      (description "电阻类型:薄膜电阻;阻值:3kΩ;精度:±0.1%;功率:62.5mW;最大工作电压:50V;温度系数:±25ppm/°C;")
      (fields (field (name "Manufacturer Part") "RT0402BRD073KL") (field (name "Manufacturer") "YAGEO(国巨)"))
      (libsource (lib "easyedapro") (part "RT0402BRD073KL"))
    )
    (comp (ref "R23")
      (value "10kΩ")
      (footprint "easyedapro:R0603")
      (description "电阻类型:厚膜电阻;阻值:10kΩ;精度:±1%;功率:100mW;最大工作电压:75V;温度系数:±100ppm/°C;")
      (fields
        (field (name "Manufacturer Part") "0603WAF1002T5E")
        (field (name "Manufacturer") "UNI-ROYAL(厚声)")
      )
      (libsource (lib "easyedapro") (part "0603WAF1002T5E"))
    )
    (comp (ref "R24")
      (value "2.5kΩ")
      (footprint "easyedapro:R0603")
      (description "阻值:2.5kΩ;精度:±0.1%;功率:62.5mW;温度系数:±25ppm/°C;")
      (fields (field (name "Manufacturer Part") "AR03BTC2501") (field (name "Manufacturer") "Viking(光颉)"))
      (libsource (lib "easyedapro") (part "AR03BTC2501"))
    )
    (comp (ref "R25")
      (value "100Ω")
      (footprint "easyedapro:R0603")
      (description "电阻类型:厚膜电阻;阻值:100Ω;精度:±1%;功率:100mW;最大工作电压:75V;温度系数:±100ppm/°C;")
      (fields (field (name "Manufacturer Part") "RC0603FR-07100RL") (field (name "Manufacturer") "YAGEO(国巨)"))
      (libsource (lib "easyedapro") (part "RC0603FR-07100RL"))
    )
    (comp (ref "R26")
      (value "100Ω")
      (footprint "easyedapro:R0603")
      (description "电阻类型:厚膜电阻;阻值:100Ω;精度:±1%;功率:100mW;最大工作电压:75V;温度系数:±100ppm/°C;")
      (fields (field (name "Manufacturer Part") "RC0603FR-07100RL") (field (name "Manufacturer") "YAGEO(国巨)"))
      (libsource (lib "easyedapro") (part "RC0603FR-07100RL"))
    )
    (comp (ref "U4")
      (value "15Ω")
      (footprint "easyedapro:RES-TH_L48.0-W12.5-P52.00-D0.8")
      (description "电阻类型:水泥电阻;阻值:15Ω;精度:±5%;功率:15W;温度系数:±300ppm/°C;")
      (fields (field (name "Manufacturer Part") "NSP15AJB-15R") (field (name "Manufacturer") "YAGEO(国巨)"))
      (libsource (lib "easyedapro") (part "NSP15AJB-15R"))
    )
    (comp (ref "U5")
      (value "TL431A")
      (footprint "easyedapro:SOT-23-3_L2.9-W1.3-P1.90-LS2.4-BR")
      (description "输出类型:可调;输入电压:37V;输出电压:2.495V~36V;输出电流:100mA;精度:±0.5%;")
      (fields (field (name "Manufacturer") "PJSEMI(平晶微)"))
      (libsource (lib "easyedapro") (part "TL431A_C411753"))
    )
    (comp (ref "U6")
      (value "DS12W-MS")
      (footprint "easyedapro:SOD-123FL_L2.7-W1.8-LS3.8-RD")
      (description "二极管配置:独立式;正向压降(Vf):550mV@1A;直流反向耐压(Vr):20V;平均整流电流(Io):1A;")
      (fields (field (name "Manufacturer") "MSKSEMI(美森科)"))
      (libsource (lib "easyedapro") (part "DS12W-MS"))
    )
    (comp (ref "C14")
      (value "100nF")
      (footprint "easyedapro:C0603")
      (description "容值:100nF;精度:±10%;额定电压:50V;材质(温度系数):X7R;")
      (fields
        (field (name "Manufacturer Part") "CL10B104KB8NNNC")
        (field (name "Manufacturer") "SAMSUNG(三星)")
      )
      (libsource (lib "easyedapro") (part "CL10B104KB8NNNC"))
    )
    (comp (ref "R28")
      (value "20kΩ")
      (footprint "easyedapro:R0603")
      (description "电阻类型:薄膜电阻;阻值:20kΩ;精度:±0.1%;功率:100mW;最大工作电压:75V;温度系数:±25ppm/°C;")
      (fields (field (name "Manufacturer Part") "RT0603BRD0720KL") (field (name "Manufacturer") "YAGEO(国巨)"))
      (libsource (lib "easyedapro") (part "RT0603BRD0720KL"))
    )
    (comp (ref "R29")
      (value "1kΩ")
      (footprint "easyedapro:R0603")
      (description "电阻类型:厚膜电阻;阻值:1kΩ;精度:±1%;功率:100mW;最大工作电压:75V;温度系数:±100ppm/°C;")
      (fields (field (name "Manufacturer Part") "RC0603FR-071KL") (field (name "Manufacturer") "YAGEO(国巨)"))
      (libsource (lib "easyedapro") (part "RC0603FR-071KL"))
    )
    (comp (ref "R30")
      (value "500Ω")
      (footprint "easyedapro:R0805")
      (description "电阻类型:薄膜电阻;阻值:500Ω;精度:±1%;功率:125mW;最大工作电压:150V;温度系数:±25ppm/°C;")
      (fields (field (name "Manufacturer Part") "ARG05FTC5000") (field (name "Manufacturer") "Viking(光颉)"))
      (libsource (lib "easyedapro") (part "ARG05FTC5000"))
    )
    (comp (ref "R31")
      (value "50Ω")
      (footprint "easyedapro:R0805")
      (description "电阻类型:薄膜电阻;阻值:50Ω;精度:±1%;功率:125mW;最大工作电压:150V;温度系数:±25ppm/°C;")
      (fields (field (name "Manufacturer Part") "ARG05FTC0500") (field (name "Manufacturer") "Viking(光颉)"))
      (libsource (lib "easyedapro") (part "ARG05FTC0500"))
    )
    (comp (ref "R32")
      (value "1kΩ")
      (footprint "easyedapro:R0603")
      (description "电阻类型:厚膜电阻;阻值:1kΩ;精度:±1%;功率:100mW;最大工作电压:75V;温度系数:±100ppm/°C;")
      (fields
        (field (name "Manufacturer Part") "0603WAF1001T5E")
        (field (name "Manufacturer") "UNI-ROYAL(厚声)")
      )
      (libsource (lib "easyedapro") (part "0603WAF1001T5E"))
    )
    (comp (ref "R33")
      (value "10kΩ")
      (footprint "easyedapro:R0805")
      (description "电阻类型:厚膜电阻;阻值:10kΩ;精度:±1%;功率:125mW;最大工作电压:150V;温度系数:±100ppm/°C;")
      (fields
        (field (name "Manufacturer Part") "0805W8F1002T5E")
        (field (name "Manufacturer") "UNI-ROYAL(厚声)")
      )
      (libsource (lib "easyedapro") (part "0805W8F1002T5E"))
    )
    (comp (ref "R36")
      (value "3kΩ")
      (footprint "easyedapro:R0603")
      (description "电阻类型:厚膜电阻;阻值:3kΩ;精度:±1%;功率:100mW;最大工作电压:75V;温度系数:±100ppm/°C;")
      (fields (field (name "Manufacturer Part") "RC0603FR-073KL") (field (name "Manufacturer") "YAGEO(国巨)"))
      (libsource (lib "easyedapro") (part "RC0603FR-073KL"))
    )
    (comp (ref "R37")
      (value "10kΩ")
      (footprint "easyedapro:R0805")
      (description "电阻类型:薄膜电阻;阻值:10kΩ;精度:±0.1%;功率:125mW;最大工作电压:150V;温度系数:±25ppm/°C;")
      (fields (field (name "Manufacturer Part") "RT0805BRD0710KL") (field (name "Manufacturer") "YAGEO(国巨)"))
      (libsource (lib "easyedapro") (part "RT0805BRD0710KL"))
    )
    (comp (ref "U8")
      (value "TL431AIDBZR")
      (footprint "easyedapro:SOT-23-3_L2.9-W1.6-P1.90-LS2.8-BR")
      (description "输出类型:可调;输入电压:-;输出电压:2.495V~36V;输出电流:100mA;精度:±1%;")
      (fields (field (name "Manufacturer") "TI(德州仪器)"))
      (libsource (lib "easyedapro") (part "TL431AIDBZR"))
    )
    (comp (ref "U9")
      (value "TLP293(GB-TPL,E(T")
      (footprint "easyedapro:SO-4_L4.6-W2.6-P1.27-LS7.0")
      (fields (field (name "Manufacturer") "TOSHIBA(东芝)"))
      (libsource (lib "easyedapro") (part "TLP293(GB-TPL,E(T"))
    )
    (comp (ref "C15")
      (value "3nF")
      (footprint "easyedapro:C0402")
      (description "容值:3nF;精度:±5%;额定电压:10V;材质(温度系数):U2J;")
      (fields
        (field (name "Manufacturer Part") "GRM1557U1A302JA01D")
        (field (name "Manufacturer") "muRata(村田)")
      )
      (libsource (lib "easyedapro") (part "GRM1557U1A302JA01D"))
    )
    (comp (ref "C16")
      (value "470pF")
      (footprint "easyedapro:C0805")
      (description "容值:470pF;精度:±5%;额定电压:50V;介电材料:金属化聚苯硫醚;工作温度:-55°C~+125°C;")
      (fields (field (name "Manufacturer Part") "ECHU1H471JX5") (field (name "Manufacturer") "PANASONIC(松下)"))
      (libsource (lib "easyedapro") (part "ECHU1H471JX5"))
    )
    (comp (ref "C17")
      (value "2.2nF")
      (footprint "easyedapro:C0603")
      (description "容值:2.2nF;精度:±1%;额定电压:50V;材质(温度系数):C0G;")
      (fields
        (field (name "Manufacturer Part") "GCM1885C1H222FA16D")
        (field (name "Manufacturer") "muRata(村田)")
      )
      (libsource (lib "easyedapro") (part "GCM1885C1H222FA16D"))
    )
    (comp (ref "R34")
      (value "1kΩ")
      (footprint "easyedapro:R0603")
      (description "电阻类型:厚膜电阻;阻值:1kΩ;精度:±1%;功率:100mW;最大工作电压:75V;温度系数:±100ppm/°C;")
      (fields
        (field (name "Manufacturer Part") "0603WAF1001T5E")
        (field (name "Manufacturer") "UNI-ROYAL(厚声)")
      )
      (libsource (lib "easyedapro") (part "0603WAF1001T5E"))
    )
    (comp (ref "R35")
      (value "1kΩ")
      (footprint "easyedapro:R0603")
      (description "电阻类型:厚膜电阻;阻值:1kΩ;精度:±1%;功率:100mW;最大工作电压:75V;温度系数:±100ppm/°C;")
      (fields
        (field (name "Manufacturer Part") "0603WAF1001T5E")
        (field (name "Manufacturer") "UNI-ROYAL(厚声)")
      )
      (libsource (lib "easyedapro") (part "0603WAF1001T5E"))
    )
    (comp (ref "U10")
      (value "UC3842AD8TR")
      (footprint "easyedapro:SOIC-8_L4.9-W3.9-P1.27-LS6.0-BL")
      (description "电源电压:10V~30V;开关频率:500kHz;")
      (fields (field (name "Manufacturer") "TI(德州仪器)"))
      (libsource (lib "easyedapro") (part "UC3842AD8TR"))
    )
    (comp (ref "U11")
      (value "8.87kΩ")
      (footprint "easyedapro:R0603")
      (description "电阻类型:厚膜电阻;阻值:8.87kΩ;精度:±1%;功率:100mW;最大工作电压:75V;温度系数:±100ppm/°C;")
      (fields (field (name "Manufacturer Part") "FRC0603F8871TS") (field (name "Manufacturer") "FOJAN(富捷)"))
      (libsource (lib "easyedapro") (part "FRC0603F8871TS"))
    )
    (comp (ref "C18")
      (value "1uF")
      (footprint "easyedapro:C1206")
      (description "容值:1uF;精度:±10%;额定电压:100V;材质(温度系数):X7R;")
      (fields
        (field (name "Manufacturer Part") "CL31B105KCHNNNE")
        (field (name "Manufacturer") "SAMSUNG(三星)")
      )
      (libsource (lib "easyedapro") (part "CL31B105KCHNNNE"))
    )
    (comp (ref "C19")
      (value "1uF")
      (footprint "easyedapro:C1206")
      (description "容值:1uF;精度:±10%;额定电压:100V;材质(温度系数):X7R;")
      (fields
        (field (name "Manufacturer Part") "CL31B105KCHNNNE")
        (field (name "Manufacturer") "SAMSUNG(三星)")
      )
      (libsource (lib "easyedapro") (part "CL31B105KCHNNNE"))
    )
    (comp (ref "C20")
      (value "1uF")
      (footprint "easyedapro:C1206")
      (description "容值:1uF;精度:±10%;额定电压:100V;材质(温度系数):X7R;")
      (fields
        (field (name "Manufacturer Part") "CL31B105KCHNNNE")
        (field (name "Manufacturer") "SAMSUNG(三星)")
      )
      (libsource (lib "easyedapro") (part "CL31B105KCHNNNE"))
    )
    (comp (ref "D4")
      (value "MB2S")
      (footprint "easyedapro:MBS_L4.7-W4.0-P2.50-LS7.0-BL")
      (description "正向压降(Vf):1.1V@800mA;直流反向耐压(Vr):200V;平均整流电流(Io):800mA;正向浪涌电流(Ifsm):30A;")
      (fields (field (name "Manufacturer") "晶导微电子"))
      (libsource (lib "easyedapro") (part "MB2S_C437884"))
    )
    (comp (ref "L16")
      (value "33uH")
      (footprint "easyedapro:IND-SMD_L7.0-W6.6_FXL0650")
      (description "电感值:33uH;精度:±20%;额定电流:2.3A;饱和电流(Isat):3A;类型:一体成型电感;")
      (fields (field (name "Manufacturer Part") "FXL0650-330-M") (field (name "Manufacturer") "cjiang(长江微电)"))
      (libsource (lib "easyedapro") (part "FXL0650-330-M"))
    )
    (comp (ref "L17")
      (value "33uH")
      (footprint "easyedapro:IND-SMD_L7.0-W6.6_FXL0650")
      (description "电感值:33uH;精度:±20%;额定电流:2.3A;饱和电流(Isat):3A;类型:一体成型电感;")
      (fields (field (name "Manufacturer Part") "FXL0650-330-M") (field (name "Manufacturer") "cjiang(长江微电)"))
      (libsource (lib "easyedapro") (part "FXL0650-330-M"))
    )
    (comp (ref "L18")
      (value "33uH")
      (footprint "easyedapro:IND-SMD_L7.0-W6.6_FXL0650")
      (description "电感值:33uH;精度:±20%;额定电流:2.3A;饱和电流(Isat):3A;类型:一体成型电感;")
      (fields (field (name "Manufacturer Part") "FXL0650-330-M") (field (name "Manufacturer") "cjiang(长江微电)"))
      (libsource (lib "easyedapro") (part "FXL0650-330-M"))
    )
    (comp (ref "L19")
      (value "33uH")
      (footprint "easyedapro:IND-SMD_L7.0-W6.6_FXL0650")
      (description "电感值:33uH;精度:±20%;额定电流:2.3A;饱和电流(Isat):3A;类型:一体成型电感;")
      (fields (field (name "Manufacturer Part") "FXL0650-330-M") (field (name "Manufacturer") "cjiang(长江微电)"))
      (libsource (lib "easyedapro") (part "FXL0650-330-M"))
    )
    (comp (ref "L20")
      (value "33uH")
      (footprint "easyedapro:IND-SMD_L7.0-W6.6_FXL0650")
      (description "电感值:33uH;精度:±20%;额定电流:2.3A;饱和电流(Isat):3A;类型:一体成型电感;")
      (fields (field (name "Manufacturer Part") "FXL0650-330-M") (field (name "Manufacturer") "cjiang(长江微电)"))
      (libsource (lib "easyedapro") (part "FXL0650-330-M"))
    )
    (comp (ref "L21")
      (value "33uH")
      (footprint "easyedapro:IND-SMD_L7.0-W6.6_FXL0650")
      (description "电感值:33uH;精度:±20%;额定电流:2.3A;饱和电流(Isat):3A;类型:一体成型电感;")
      (fields (field (name "Manufacturer Part") "FXL0650-330-M") (field (name "Manufacturer") "cjiang(长江微电)"))
      (libsource (lib "easyedapro") (part "FXL0650-330-M"))
    )
    (comp (ref "U13")
      (value "RT-C14-C0B-AA")
      (footprint "easyedapro:AC-TH_RT-C14-C0B-AA")
      (fields (field (name "Manufacturer") "ROCKTEK(富力隆)"))
      (libsource (lib "easyedapro") (part "RT-C14-C0B-AA"))
    )
    (comp (ref "U14")
      (value "~")
      (footprint "easyedapro:反激变压器_封装")
      (libsource (lib "easyedapro") (part "反激变压器_自定义"))
    )
  )
  (nets
    (net (code "1") (name "GND") (class "Default")
      (node (ref "C1") (pin "2") (pinfunction "2_2") (pintype "input"))
      (node (ref "C10") (pin "2") (pinfunction "2_2") (pintype "input"))
      (node (ref "C11") (pin "2") (pinfunction "2_2") (pintype "unspecified"))
      (node (ref "C12") (pin "2") (pinfunction "2_2") (pintype "unspecified"))
      (node (ref "C13") (pin "2") (pinfunction "2_2") (pintype "input"))
      (node (ref "C16") (pin "2") (pinfunction "2_2") (pintype "input"))
      (node (ref "C17") (pin "1") (pinfunction "1_1") (pintype "unspecified"))
      (node (ref "C19") (pin "1") (pinfunction "1_1") (pintype "unspecified"))
      (node (ref "C2") (pin "2") (pinfunction "2_2") (pintype "input"))
      (node (ref "C20") (pin "2") (pinfunction "2_2") (pintype "unspecified"))
      (node (ref "C27") (pin "2") (pinfunction "2_2") (pintype "input"))
      (node (ref "C28") (pin "2") (pinfunction "2_2") (pintype "input"))
      (node (ref "C29") (pin "2") (pinfunction "2_2") (pintype "input"))
      (node (ref "C3") (pin "2") (pinfunction "2_2") (pintype "input"))
      (node (ref "C30") (pin "2") (pinfunction "2_2") (pintype "input"))
      (node (ref "C4") (pin "2") (pinfunction "2_2") (pintype "input"))
      (node (ref "C5") (pin "2") (pinfunction "2_2") (pintype "input"))
      (node (ref "C6") (pin "2") (pinfunction "2_2") (pintype "input"))
      (node (ref "D4") (pin "4") (pinfunction "-_4") (pintype "unspecified"))
      (node (ref "P4") (pin "1") (pinfunction "1_1") (pintype "input"))
      (node (ref "P6") (pin "1") (pinfunction "1_1") (pintype "input"))
      (node (ref "R10") (pin "2") (pinfunction "2_2") (pintype "unspecified"))
      (node (ref "R24") (pin "2") (pinfunction "2_2") (pintype "unspecified"))
      (node (ref "R33") (pin "1") (pinfunction "1_1") (pintype "input"))
      (node (ref "R36") (pin "1") (pinfunction "1_1") (pintype "input"))
      (node (ref "R37") (pin "1") (pinfunction "1_1") (pintype "input"))
      (node (ref "U10") (pin "5") (pinfunction "GND_5") (pintype "input"))
      (node (ref "U12") (pin "3") (pinfunction "2A_3") (pintype "input"))
      (node (ref "U12") (pin "4") (pinfunction "2B_4") (pintype "input"))
      (node (ref "U12") (pin "5") (pinfunction "3A_5") (pintype "input"))
      (node (ref "U12") (pin "6") (pinfunction "3B_6") (pintype "input"))
      (node (ref "U12") (pin "7") (pinfunction "4A_7") (pintype "input"))
      (node (ref "U12") (pin "9") (pinfunction "5A_9") (pintype "input"))
      (node (ref "U13") (pin "1") (pinfunction "E_1") (pintype "unspecified"))
      (node (ref "U15") (pin "1") (pinfunction "1_1") (pintype "unspecified"))
      (node (ref "U2") (pin "3") (pinfunction "A_3") (pintype "unspecified"))
      (node (ref "U5") (pin "3") (pinfunction "A_3") (pintype "unspecified"))
      (node (ref "U8") (pin "3") (pinfunction "ANODE_3") (pintype "unspecified"))
    )
    (net (code "2") (name "Ics") (class "Default")
      (node (ref "Q1") (pin "3") (pinfunction "S_3") (pintype "unspecified"))
      (node (ref "R35") (pin "1") (pinfunction "1_1") (pintype "input"))
      (node (ref "U15") (pin "2") (pinfunction "2_2") (pintype "unspecified"))
    )
    (net (code "3") (name "Net-(C19-Pad2)") (class "Default")
      (node (ref "C19") (pin "2") (pinfunction "2_2") (pintype "unspecified"))
      (node (ref "D4") (pin "2") (pinfunction "AC_2") (pintype "unspecified"))
      (node (ref "L16") (pin "2") (pinfunction "2_2") (pintype "unspecified"))
      (node (ref "L17") (pin "2") (pinfunction "2_2") (pintype "unspecified"))
      (node (ref "L18") (pin "2") (pinfunction "2_2") (pintype "unspecified"))
    )
    (net (code "4") (name "Net-(C20-Pad1)") (class "Default")
      (node (ref "C20") (pin "1") (pinfunction "1_1") (pintype "unspecified"))
      (node (ref "D4") (pin "1") (pinfunction "AC_1") (pintype "unspecified"))
      (node (ref "L19") (pin "2") (pinfunction "2_2") (pintype "unspecified"))
      (node (ref "L20") (pin "2") (pinfunction "2_2") (pintype "unspecified"))
      (node (ref "L21") (pin "2") (pinfunction "2_2") (pintype "unspecified"))
    )
    (net (code "5") (name "Net-(D1-K)") (class "Default")
      (node (ref "C7") (pin "1") (pinfunction "1_1") (pintype "unspecified"))
      (node (ref "C8") (pin "1") (pinfunction "1_1") (pintype "unspecified"))
      (node (ref "C9") (pin "1") (pinfunction "1_1") (pintype "unspecified"))
      (node (ref "D1") (pin "1") (pinfunction "K_1") (pintype "unspecified"))
      (node (ref "R5") (pin "1") (pinfunction "1_1") (pintype "unspecified"))
    )
    (net (code "6") (name "Net-(D2-K)") (class "Default")
      (node (ref "C27") (pin "1") (pinfunction "1_1") (pintype "input"))
      (node (ref "C28") (pin "1") (pinfunction "1_1") (pintype "input"))
      (node (ref "C29") (pin "1") (pinfunction "1_1") (pintype "input"))
      (node (ref "C30") (pin "1") (pinfunction "1_1") (pintype "input"))
      (node (ref "D2") (pin "1") (pinfunction "K_1") (pintype "unspecified"))
      (node (ref "R7") (pin "1") (pinfunction "1_1") (pintype "unspecified"))
    )
    (net (code "7") (name "Net-(D3-K)") (class "Default")
      (node (ref "C11") (pin "1") (pinfunction "1_1") (pintype "unspecified"))
      (node (ref "C12") (pin "1") (pinfunction "1_1") (pintype "unspecified"))
      (node (ref "D3") (pin "1") (pinfunction "K_1") (pintype "unspecified"))
      (node (ref "U4") (pin "1") (pinfunction "1_1") (pintype "unspecified"))
    )
    (net (code "8") (name "Net-(L1-Pad2)") (class "Default")
      (node (ref "L1") (pin "2") (pinfunction "2_2") (pintype "unspecified"))
      (node (ref "L4") (pin "1") (pinfunction "1_1") (pintype "unspecified"))
    )
    (net (code "9") (name "Net-(L2-Pad1)") (class "Default")
      (node (ref "L2") (pin "1") (pinfunction "1_1") (pintype "unspecified"))
      (node (ref "L4") (pin "2") (pinfunction "2_2") (pintype "unspecified"))
    )
    (net (code "10") (name "Net-(L2-Pad2)") (class "Default")
      (node (ref "L2") (pin "2") (pinfunction "2_2") (pintype "unspecified"))
      (node (ref "L5") (pin "1") (pinfunction "1_1") (pintype "unspecified"))
    )
    (net (code "11") (name "Net-(L3-Pad1)") (class "Default")
      (node (ref "L3") (pin "1") (pinfunction "1_1") (pintype "unspecified"))
      (node (ref "L5") (pin "2") (pinfunction "2_2") (pintype "unspecified"))
    )
    (net (code "12") (name "Net-(L3-Pad2)") (class "Default")
      (node (ref "L3") (pin "2") (pinfunction "2_2") (pintype "unspecified"))
      (node (ref "L6") (pin "1") (pinfunction "1_1") (pintype "unspecified"))
    )
    (net (code "13") (name "Net-(L10-Pad1)") (class "Default")
      (node (ref "L10") (pin "1") (pinfunction "1_1") (pintype "unspecified"))
      (node (ref "L7") (pin "2") (pinfunction "2_2") (pintype "unspecified"))
    )
    (net (code "14") (name "Net-(L10-Pad2)") (class "Default")
      (node (ref "L10") (pin "2") (pinfunction "2_2") (pintype "unspecified"))
      (node (ref "L8") (pin "1") (pinfunction "1_1") (pintype "unspecified"))
    )
    (net (code "15") (name "Net-(L11-Pad1)") (class "Default")
      (node (ref "L11") (pin "1") (pinfunction "1_1") (pintype "unspecified"))
      (node (ref "L8") (pin "2") (pinfunction "2_2") (pintype "unspecified"))
    )
    (net (code "16") (name "Net-(L11-Pad2)") (class "Default")
      (node (ref "L11") (pin "2") (pinfunction "2_2") (pintype "unspecified"))
      (node (ref "L9") (pin "1") (pinfunction "1_1") (pintype "unspecified"))
    )
    (net (code "17") (name "Net-(L12-Pad1)") (class "Default")
      (node (ref "L12") (pin "1") (pinfunction "1_1") (pintype "unspecified"))
      (node (ref "L9") (pin "2") (pinfunction "2_2") (pintype "unspecified"))
    )
    (net (code "18") (name "Net-(L12-Pad2)") (class "Default")
      (node (ref "L12") (pin "2") (pinfunction "2_2") (pintype "unspecified"))
      (node (ref "L13") (pin "1") (pinfunction "1_1") (pintype "unspecified"))
    )
    (net (code "19") (name "Net-(L13-Pad2)") (class "Default")
      (node (ref "L13") (pin "2") (pinfunction "2_2") (pintype "unspecified"))
      (node (ref "L15") (pin "1") (pinfunction "1_1") (pintype "unspecified"))
    )
    (net (code "20") (name "Net-(L14-Pad1)") (class "Default")
      (node (ref "L14") (pin "1") (pinfunction "1_1") (pintype "unspecified"))
      (node (ref "L15") (pin "2") (pinfunction "2_2") (pintype "unspecified"))
    )
    (net (code "21") (name "Net-(L14-Pad2)") (class "Default")
      (node (ref "L14") (pin "2") (pinfunction "2_2") (pintype "unspecified"))
      (node (ref "P6") (pin "2") (pinfunction "2_2") (pintype "input"))
      (node (ref "R25") (pin "2") (pinfunction "2_2") (pintype "input"))
      (node (ref "R26") (pin "2") (pinfunction "2_2") (pintype "input"))
    )
    (net (code "22") (name "Net-(R1-Pad2)") (class "Default")
      (node (ref "R1") (pin "2") (pinfunction "2_2") (pintype "unspecified"))
      (node (ref "R2") (pin "1") (pinfunction "1_1") (pintype "unspecified"))
    )
    (net (code "23") (name "Net-(R2-Pad2)") (class "Default")
      (node (ref "R2") (pin "2") (pinfunction "2_2") (pintype "unspecified"))
      (node (ref "R3") (pin "1") (pinfunction "1_1") (pintype "unspecified"))
    )
    (net (code "24") (name "Net-(R3-Pad2)") (class "Default")
      (node (ref "R3") (pin "2") (pinfunction "2_2") (pintype "unspecified"))
      (node (ref "R4") (pin "1") (pinfunction "1_1") (pintype "unspecified"))
    )
    (net (code "25") (name "Net-(R30-Pad2)") (class "Default")
      (node (ref "R30") (pin "2") (pinfunction "2_2") (pintype "unspecified"))
      (node (ref "R31") (pin "1") (pinfunction "1_1") (pintype "unspecified"))
    )
    (net (code "26") (name "Net-(U2-K)") (class "Default")
      (node (ref "C10") (pin "1") (pinfunction "1_1") (pintype "input"))
      (node (ref "L1") (pin "1") (pinfunction "1_1") (pintype "unspecified"))
      (node (ref "R27") (pin "1") (pinfunction "1_1") (pintype "input"))
      (node (ref "R7") (pin "2") (pinfunction "2_2") (pintype "unspecified"))
      (node (ref "R8") (pin "1") (pinfunction "1_1") (pintype "input"))
      (node (ref "U2") (pin "2") (pinfunction "K_2") (pintype "unspecified"))
      (node (ref "U3") (pin "1") (pinfunction "C_1") (pintype "unspecified"))
    )
    (net (code "27") (name "Net-(U2-R)") (class "Default")
      (node (ref "R10") (pin "1") (pinfunction "1_1") (pintype "unspecified"))
      (node (ref "R27") (pin "2") (pinfunction "2_2") (pintype "input"))
      (node (ref "R8") (pin "2") (pinfunction "2_2") (pintype "input"))
      (node (ref "U2") (pin "1") (pinfunction "R_1") (pintype "unspecified"))
    )
    (net (code "28") (name "Net-(U3-A)") (class "Default")
      (node (ref "U18") (pin "1") (pinfunction "1_1") (pintype "unspecified"))
      (node (ref "U19") (pin "1") (pinfunction "1_1") (pintype "unspecified"))
      (node (ref "U20") (pin "1") (pinfunction "1_1") (pintype "unspecified"))
      (node (ref "U21") (pin "1") (pinfunction "1_1") (pintype "unspecified"))
      (node (ref "U22") (pin "1") (pinfunction "1_1") (pintype "unspecified"))
      (node (ref "U23") (pin "1") (pinfunction "1_1") (pintype "unspecified"))
      (node (ref "U24") (pin "1") (pinfunction "1_1") (pintype "unspecified"))
      (node (ref "U25") (pin "1") (pinfunction "1_1") (pintype "unspecified"))
      (node (ref "U26") (pin "1") (pinfunction "1_1") (pintype "unspecified"))
      (node (ref "U27") (pin "1") (pinfunction "1_1") (pintype "unspecified"))
      (node (ref "U3") (pin "2") (pinfunction "A_2") (pintype "unspecified"))
    )
    (net (code "29") (name "Net-(U5-K)") (class "Default")
      (node (ref "C13") (pin "1") (pinfunction "1_1") (pintype "input"))
      (node (ref "L7") (pin "1") (pinfunction "1_1") (pintype "unspecified"))
      (node (ref "R22") (pin "1") (pinfunction "1_1") (pintype "input"))
      (node (ref "R23") (pin "1") (pinfunction "1_1") (pintype "input"))
      (node (ref "U4") (pin "2") (pinfunction "2_2") (pintype "unspecified"))
      (node (ref "U5") (pin "2") (pinfunction "K_2") (pintype "unspecified"))
      (node (ref "U6") (pin "1") (pinfunction "C_1") (pintype "unspecified"))
    )
    (net (code "30") (name "Net-(U5-R)") (class "Default")
      (node (ref "R22") (pin "2") (pinfunction "2_2") (pintype "input"))
      (node (ref "R23") (pin "2") (pinfunction "2_2") (pintype "input"))
      (node (ref "R24") (pin "1") (pinfunction "1_1") (pintype "unspecified"))
      (node (ref "U5") (pin "1") (pinfunction "R_1") (pintype "unspecified"))
    )
    (net (code "31") (name "Net-(U6-A)") (class "Default")
      (node (ref "R25") (pin "1") (pinfunction "1_1") (pintype "input"))
      (node (ref "R26") (pin "1") (pinfunction "1_1") (pintype "input"))
      (node (ref "U6") (pin "2") (pinfunction "A_2") (pintype "unspecified"))
    )
    (net (code "32") (name "Net-(U8-CATHODE)") (class "Default")
      (node (ref "C14") (pin "1") (pinfunction "1_1") (pintype "unspecified"))
      (node (ref "R29") (pin "1") (pinfunction "1_1") (pintype "input"))
      (node (ref "U8") (pin "1") (pinfunction "CATHODE_1") (pintype "unspecified"))
      (node (ref "U9") (pin "2") (pinfunction "Cathode_2") (pintype "unspecified"))
    )
    (net (code "33") (name "Net-(U8-REF)") (class "Default")
      (node (ref "C14") (pin "2") (pinfunction "2_2") (pintype "unspecified"))
      (node (ref "R28") (pin "1") (pinfunction "1_1") (pintype "unspecified"))
      (node (ref "R36") (pin "2") (pinfunction "2_2") (pintype "input"))
      (node (ref "R37") (pin "2") (pinfunction "2_2") (pintype "input"))
      (node (ref "U8") (pin "2") (pinfunction "REF_2") (pintype "unspecified"))
    )
    (net (code "34") (name "Net-(U9-Anode)") (class "Default")
      (node (ref "R29") (pin "2") (pinfunction "2_2") (pintype "input"))
      (node (ref "R30") (pin "1") (pinfunction "1_1") (pintype "unspecified"))
      (node (ref "U9") (pin "1") (pinfunction "Anode_1") (pintype "unspecified"))
    )
    (net (code "35") (name "Net-(U9-Emitter)") (class "Default")
      (node (ref "R32") (pin "2") (pinfunction "2_2") (pintype "input"))
      (node (ref "R33") (pin "2") (pinfunction "2_2") (pintype "input"))
      (node (ref "U9") (pin "3") (pinfunction "Emitter_3") (pintype "unspecified"))
    )
    (net (code "36") (name "Net-(U10-COMP)") (class "Default")
      (node (ref "C15") (pin "1") (pinfunction "1_1") (pintype "unspecified"))
      (node (ref "R34") (pin "2") (pinfunction "2_2") (pintype "input"))
      (node (ref "U10") (pin "1") (pinfunction "COMP_1") (pintype "input"))
    )
    (net (code "37") (name "Net-(U10-ISENSE)") (class "Default")
      (node (ref "C16") (pin "1") (pinfunction "1_1") (pintype "input"))
      (node (ref "R35") (pin "2") (pinfunction "2_2") (pintype "input"))
      (node (ref "U10") (pin "3") (pinfunction "ISENSE_3") (pintype "input"))
    )
    (net (code "38") (name "Net-(U10-RT{slash}CT)") (class "Default")
      (node (ref "C17") (pin "2") (pinfunction "2_2") (pintype "unspecified"))
      (node (ref "U10") (pin "4") (pinfunction "RT/CT_4") (pintype "input"))
      (node (ref "U11") (pin "1") (pinfunction "1_1") (pintype "unspecified"))
    )
    (net (code "39") (name "Net-(U13-L)") (class "Default")
      (node (ref "U13") (pin "3") (pinfunction "L_3") (pintype "unspecified"))
      (node (ref "U14") (pin "1") (pinfunction "1A_1") (pintype "input"))
    )
    (net (code "40") (name "Net-(U13-N)") (class "Default")
      (node (ref "U13") (pin "2") (pinfunction "N_2") (pintype "unspecified"))
      (node (ref "U14") (pin "2") (pinfunction "1B_2") (pintype "input"))
    )
    (net (code "41") (name "Net-(U14-2A)") (class "Default")
      (node (ref "U14") (pin "3") (pinfunction "2A_3") (pintype "input"))
      (node (ref "U14") (pin "4") (pinfunction "2B_4") (pintype "input"))
      (node (ref "U14") (pin "5") (pinfunction "3A_5") (pintype "input"))
    )
    (net (code "42") (name "Net-(U14-3B)") (class "Default")
      (node (ref "U14") (pin "6") (pinfunction "3B_6") (pintype "input"))
      (node (ref "U14") (pin "7") (pinfunction "4A_7") (pintype "input"))
      (node (ref "U14") (pin "8") (pinfunction "4B_8") (pintype "input"))
    )
    (net (code "43") (name "Net-(U14-5A)") (class "Default")
      (node (ref "C18") (pin "2") (pinfunction "2_2") (pintype "unspecified"))
      (node (ref "L16") (pin "1") (pinfunction "1_1") (pintype "unspecified"))
      (node (ref "L17") (pin "1") (pinfunction "1_1") (pintype "unspecified"))
      (node (ref "L18") (pin "1") (pinfunction "1_1") (pintype "unspecified"))
      (node (ref "U14") (pin "9") (pinfunction "5A_9") (pintype "input"))
    )
    (net (code "44") (name "Net-(U14-5B)") (class "Default")
      (node (ref "C18") (pin "1") (pinfunction "1_1") (pintype "unspecified"))
      (node (ref "L19") (pin "1") (pinfunction "1_1") (pintype "unspecified"))
      (node (ref "L20") (pin "1") (pinfunction "1_1") (pintype "unspecified"))
      (node (ref "L21") (pin "1") (pinfunction "1_1") (pintype "unspecified"))
      (node (ref "U14") (pin "10") (pinfunction "5B_10") (pintype "input"))
    )
    (net (code "45") (name "PWM") (class "Default")
      (node (ref "Q1") (pin "1") (pinfunction "G_1") (pintype "unspecified"))
      (node (ref "U10") (pin "6") (pinfunction "OUTPUT_6") (pintype "input"))
    )
    (net (code "46") (name "Tin_1") (class "Default")
      (node (ref "C1") (pin "1") (pinfunction "1_1") (pintype "input"))
      (node (ref "C2") (pin "1") (pinfunction "1_1") (pintype "input"))
      (node (ref "C3") (pin "1") (pinfunction "1_1") (pintype "input"))
      (node (ref "C4") (pin "1") (pinfunction "1_1") (pintype "input"))
      (node (ref "C5") (pin "1") (pinfunction "1_1") (pintype "input"))
      (node (ref "C6") (pin "1") (pinfunction "1_1") (pintype "input"))
      (node (ref "C7") (pin "2") (pinfunction "2_2") (pintype "unspecified"))
      (node (ref "C8") (pin "2") (pinfunction "2_2") (pintype "unspecified"))
      (node (ref "C9") (pin "2") (pinfunction "2_2") (pintype "unspecified"))
      (node (ref "D4") (pin "3") (pinfunction "+_3") (pintype "unspecified"))
      (node (ref "R1") (pin "1") (pinfunction "1_1") (pintype "unspecified"))
      (node (ref "R5") (pin "2") (pinfunction "2_2") (pintype "unspecified"))
      (node (ref "U12") (pin "1") (pinfunction "1A_1") (pintype "input"))
    )
    (net (code "47") (name "Tin_2") (class "Default")
      (node (ref "D1") (pin "2") (pinfunction "A_2") (pintype "unspecified"))
      (node (ref "Q1") (pin "2") (pinfunction "D_2") (pintype "unspecified"))
      (node (ref "U12") (pin "2") (pinfunction "1B_2") (pintype "input"))
    )
    (net (code "48") (name "To5_2") (class "Default")
      (node (ref "D2") (pin "2") (pinfunction "A_2") (pintype "unspecified"))
      (node (ref "U12") (pin "10") (pinfunction "5B_10") (pintype "input"))
    )
    (net (code "49") (name "To15_2") (class "Default")
      (node (ref "D3") (pin "2") (pinfunction "A_2") (pintype "unspecified"))
      (node (ref "U12") (pin "8") (pinfunction "4B_8") (pintype "input"))
    )
    (net (code "50") (name "Vcc") (class "Default")
      (node (ref "R4") (pin "2") (pinfunction "2_2") (pintype "unspecified"))
      (node (ref "U10") (pin "7") (pinfunction "VCC_7") (pintype "input"))
    )
    (net (code "51") (name "Vfb") (class "Default")
      (node (ref "C15") (pin "2") (pinfunction "2_2") (pintype "unspecified"))
      (node (ref "R32") (pin "1") (pinfunction "1_1") (pintype "input"))
      (node (ref "R34") (pin "1") (pinfunction "1_1") (pintype "input"))
      (node (ref "U10") (pin "2") (pinfunction "FB_2") (pintype "input"))
    )
    (net (code "52") (name "Vo5r") (class "Default")
      (node (ref "L6") (pin "2") (pinfunction "2_2") (pintype "unspecified"))
      (node (ref "P4") (pin "2") (pinfunction "2_2") (pintype "input"))
      (node (ref "R28") (pin "2") (pinfunction "2_2") (pintype "unspecified"))
      (node (ref "R31") (pin "2") (pinfunction "2_2") (pintype "unspecified"))
      (node (ref "U18") (pin "2") (pinfunction "2_2") (pintype "unspecified"))
      (node (ref "U19") (pin "2") (pinfunction "2_2") (pintype "unspecified"))
      (node (ref "U20") (pin "2") (pinfunction "2_2") (pintype "unspecified"))
      (node (ref "U21") (pin "2") (pinfunction "2_2") (pintype "unspecified"))
      (node (ref "U22") (pin "2") (pinfunction "2_2") (pintype "unspecified"))
      (node (ref "U23") (pin "2") (pinfunction "2_2") (pintype "unspecified"))
      (node (ref "U24") (pin "2") (pinfunction "2_2") (pintype "unspecified"))
      (node (ref "U25") (pin "2") (pinfunction "2_2") (pintype "unspecified"))
      (node (ref "U26") (pin "2") (pinfunction "2_2") (pintype "unspecified"))
      (node (ref "U27") (pin "2") (pinfunction "2_2") (pintype "unspecified"))
    )
    (net (code "53") (name "Vref") (class "Default")
      (node (ref "U10") (pin "8") (pinfunction "VREF_8") (pintype "input"))
      (node (ref "U11") (pin "2") (pinfunction "2_2") (pintype "unspecified"))
      (node (ref "U9") (pin "4") (pinfunction "Collector_4") (pintype "unspecified"))
    )
  )
)
